# BEP33_rev1.net
KiCad netlist of a schematic drawn in EAGLE
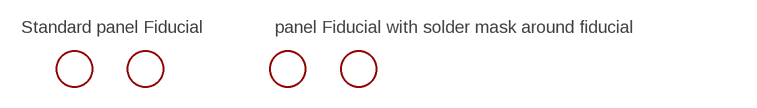
[diagram p0: schematic, sheet 1]
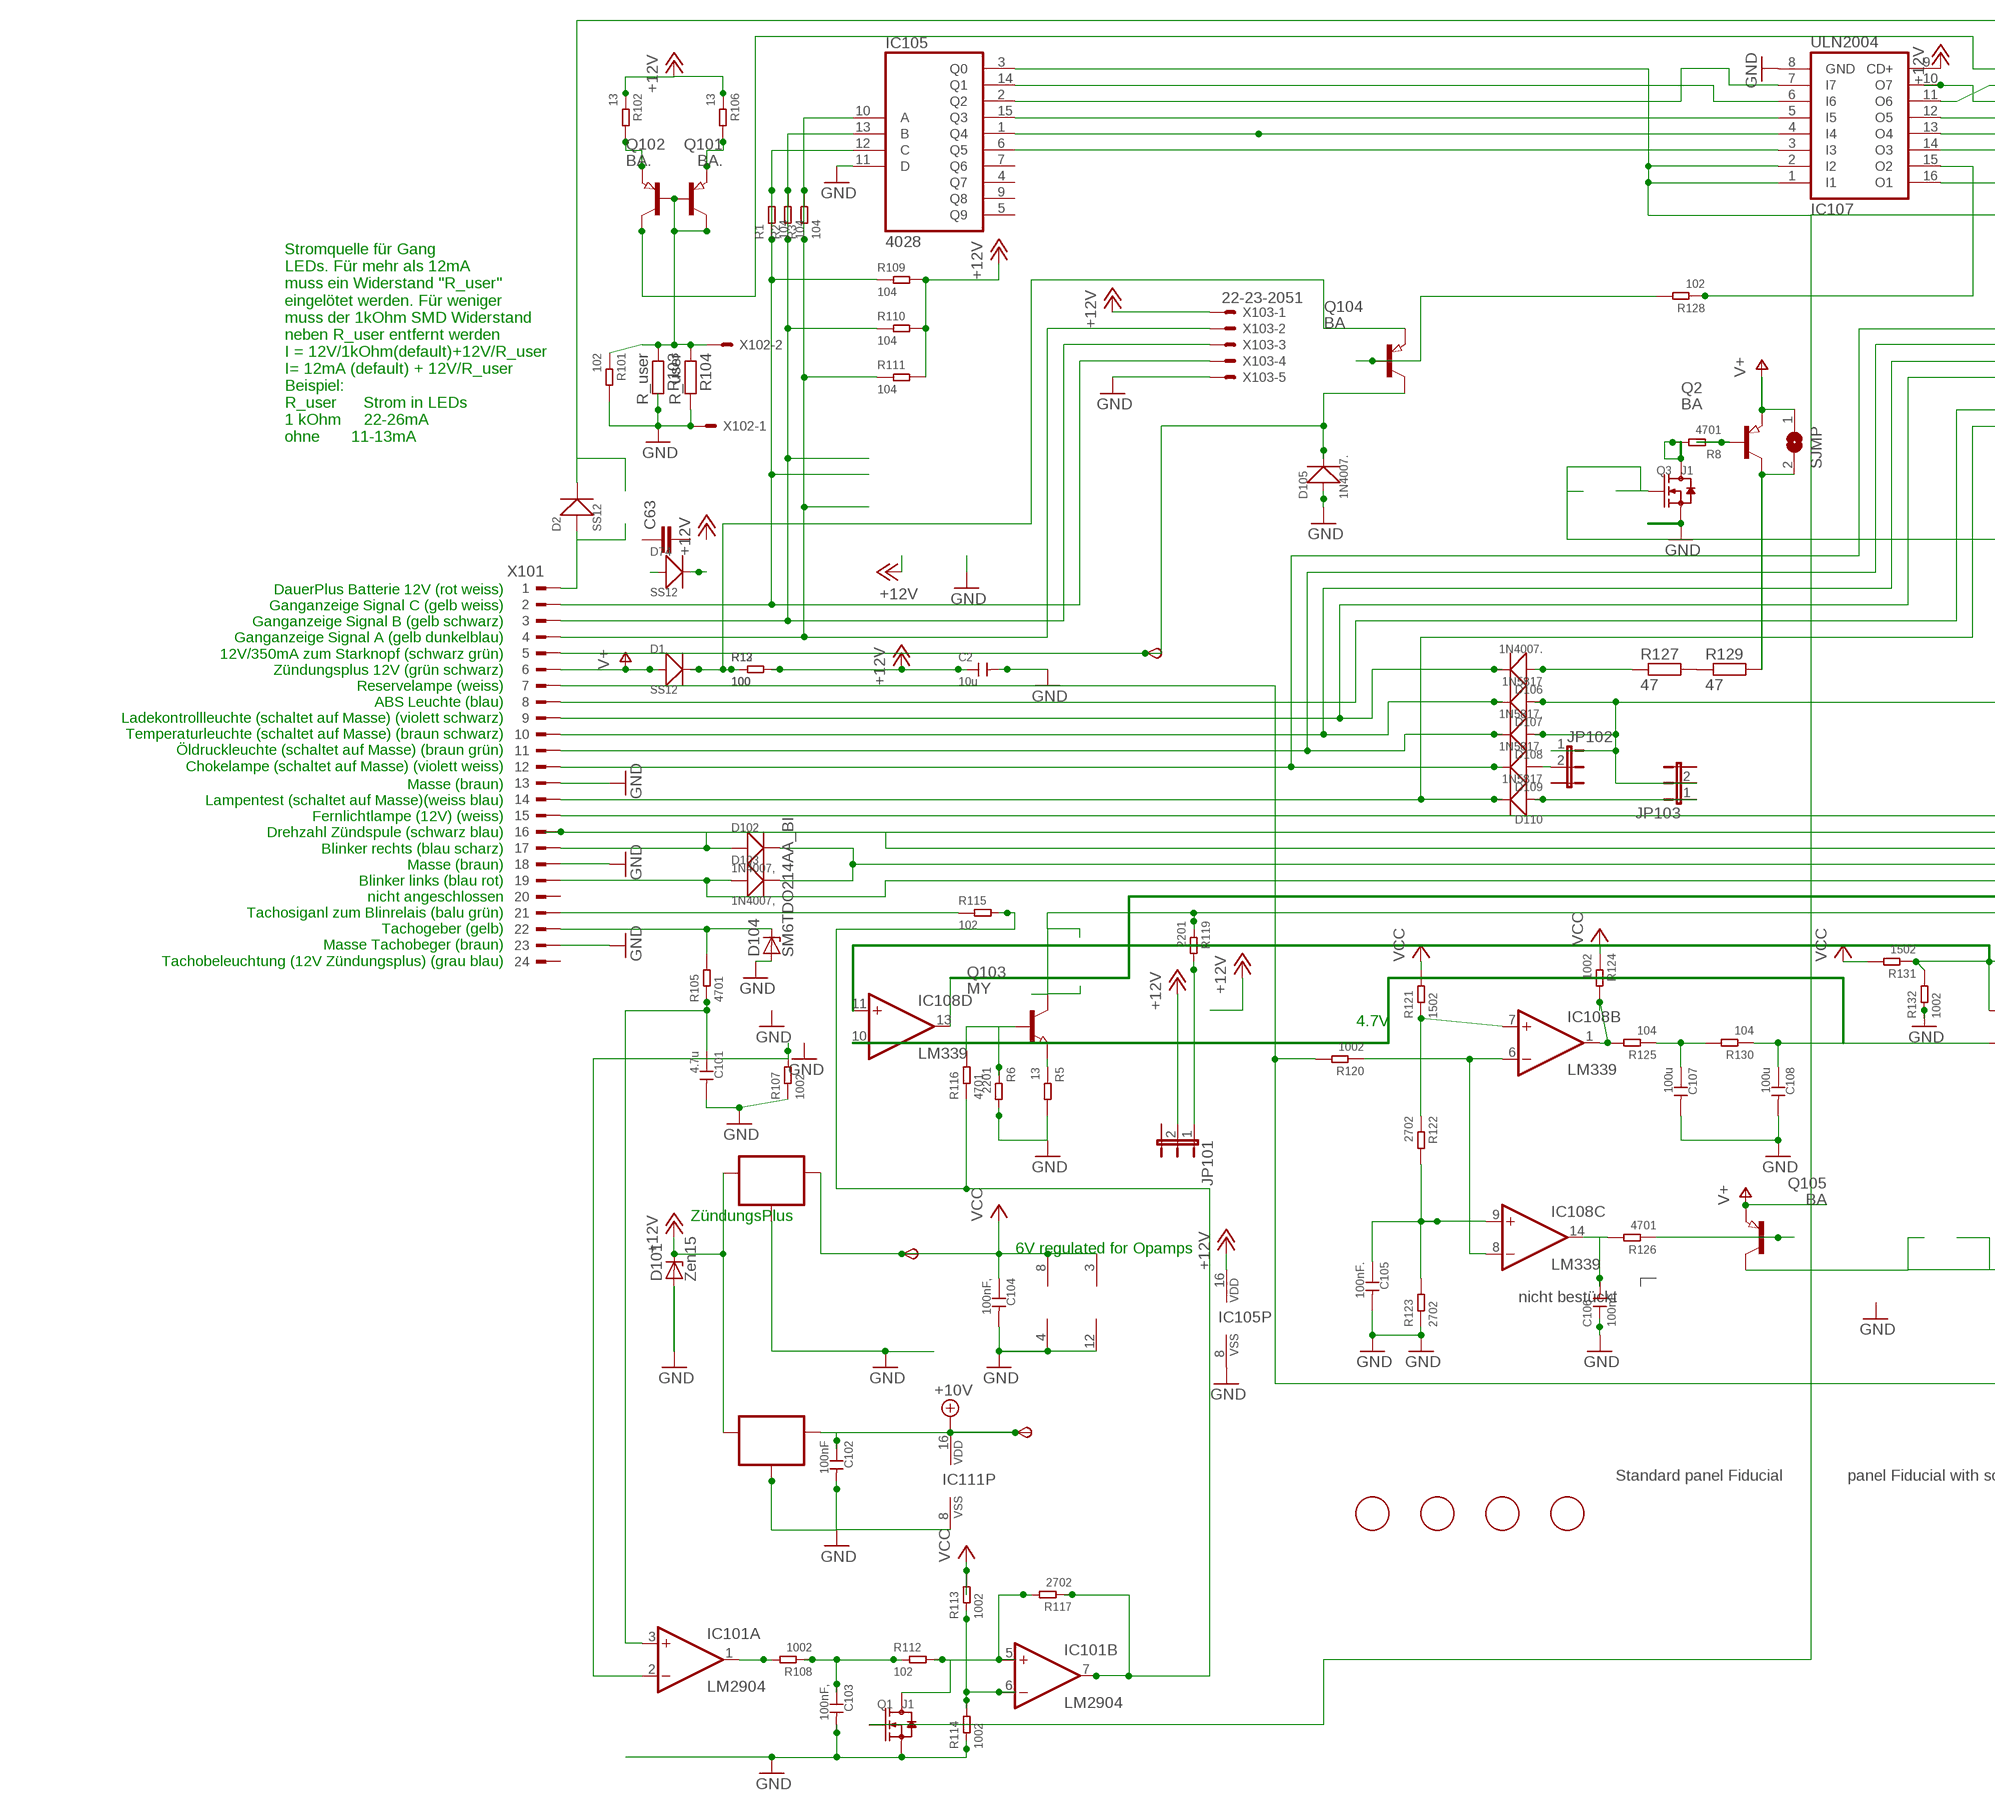
[diagram p1: schematic, sheet 2, part 1 of 2]
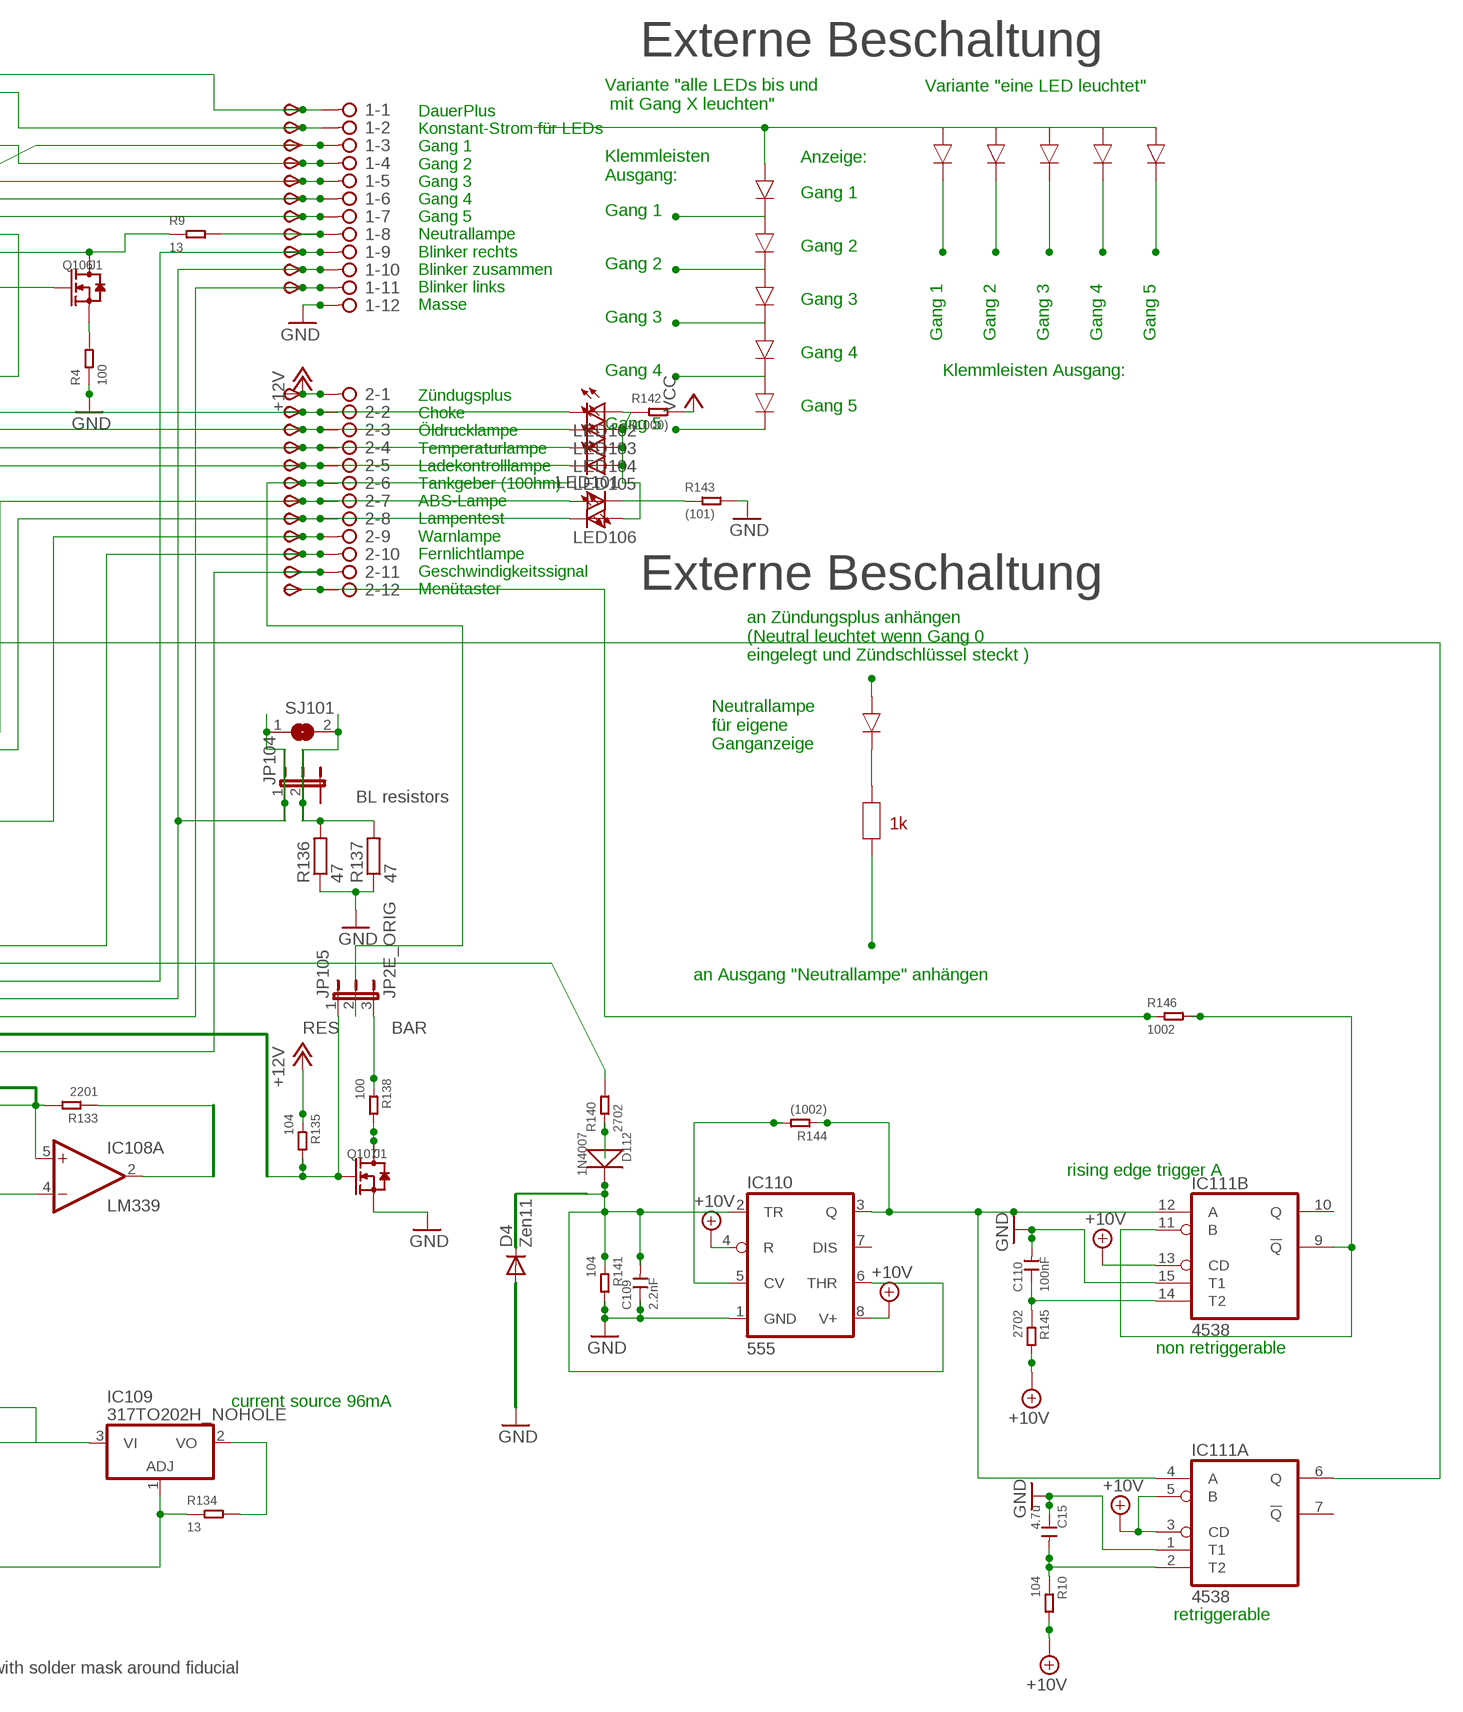
[diagram p2: schematic, sheet 2, part 2 of 2]
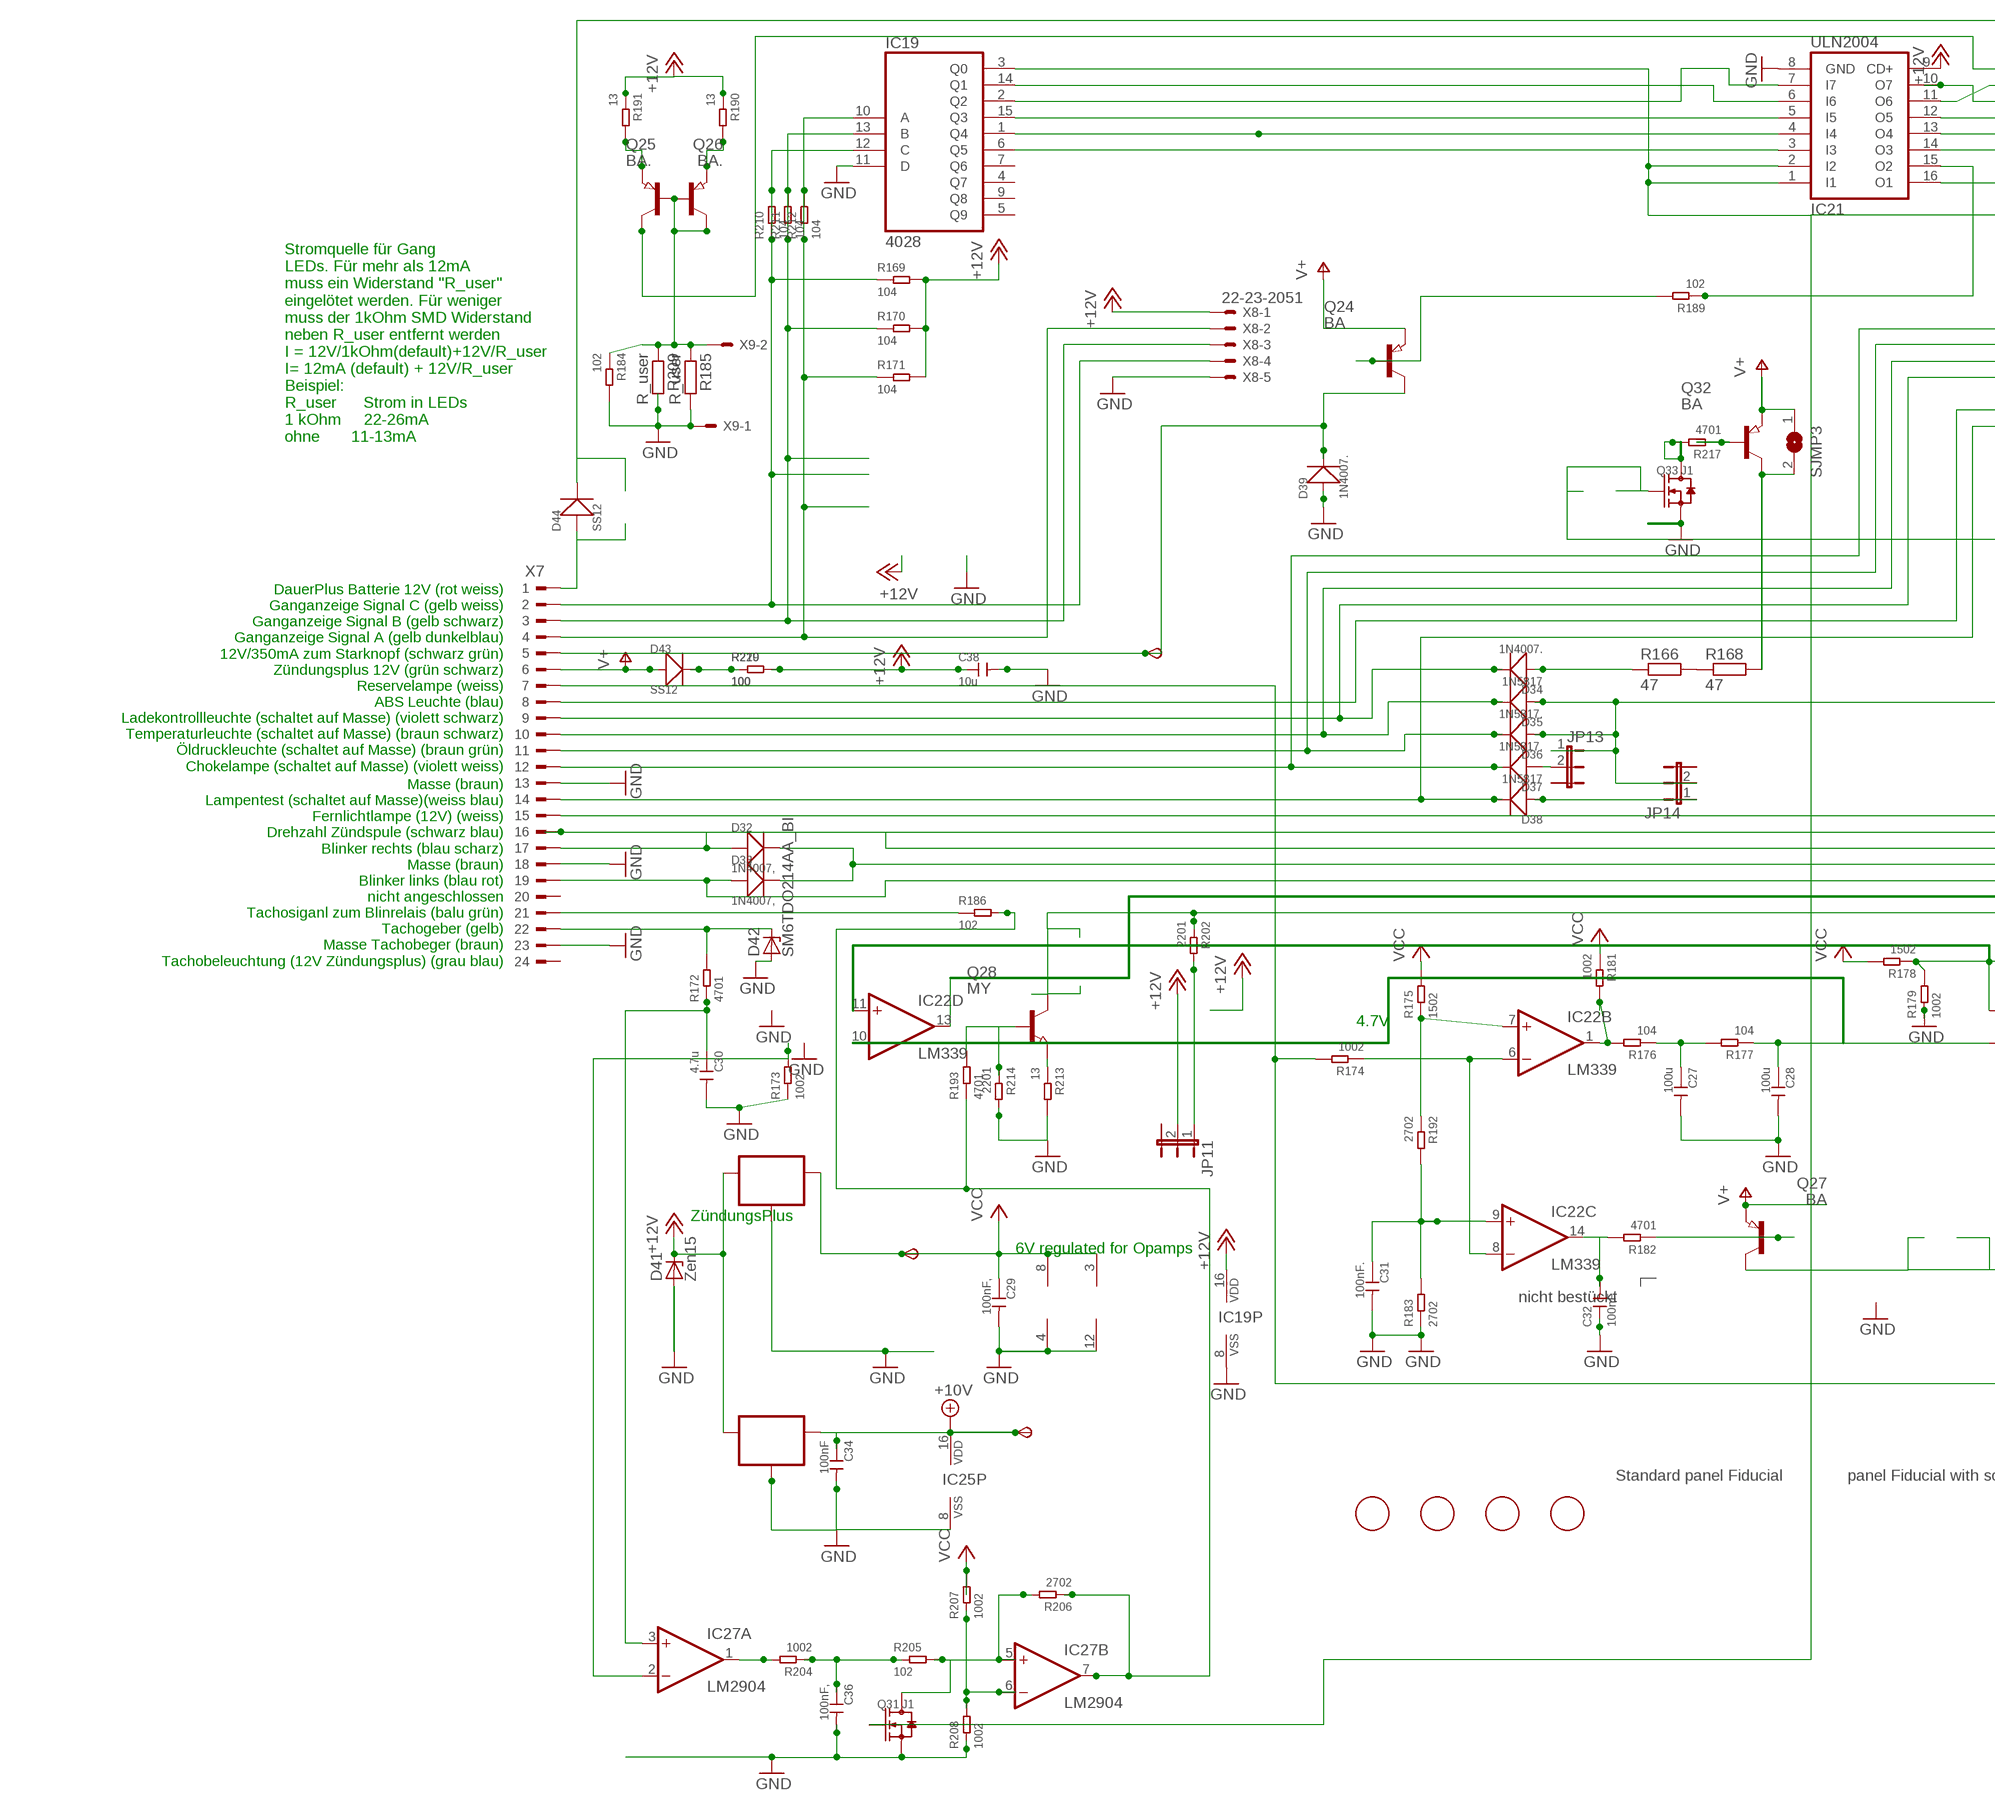
[diagram p3: schematic, sheet 3, part 1 of 2]
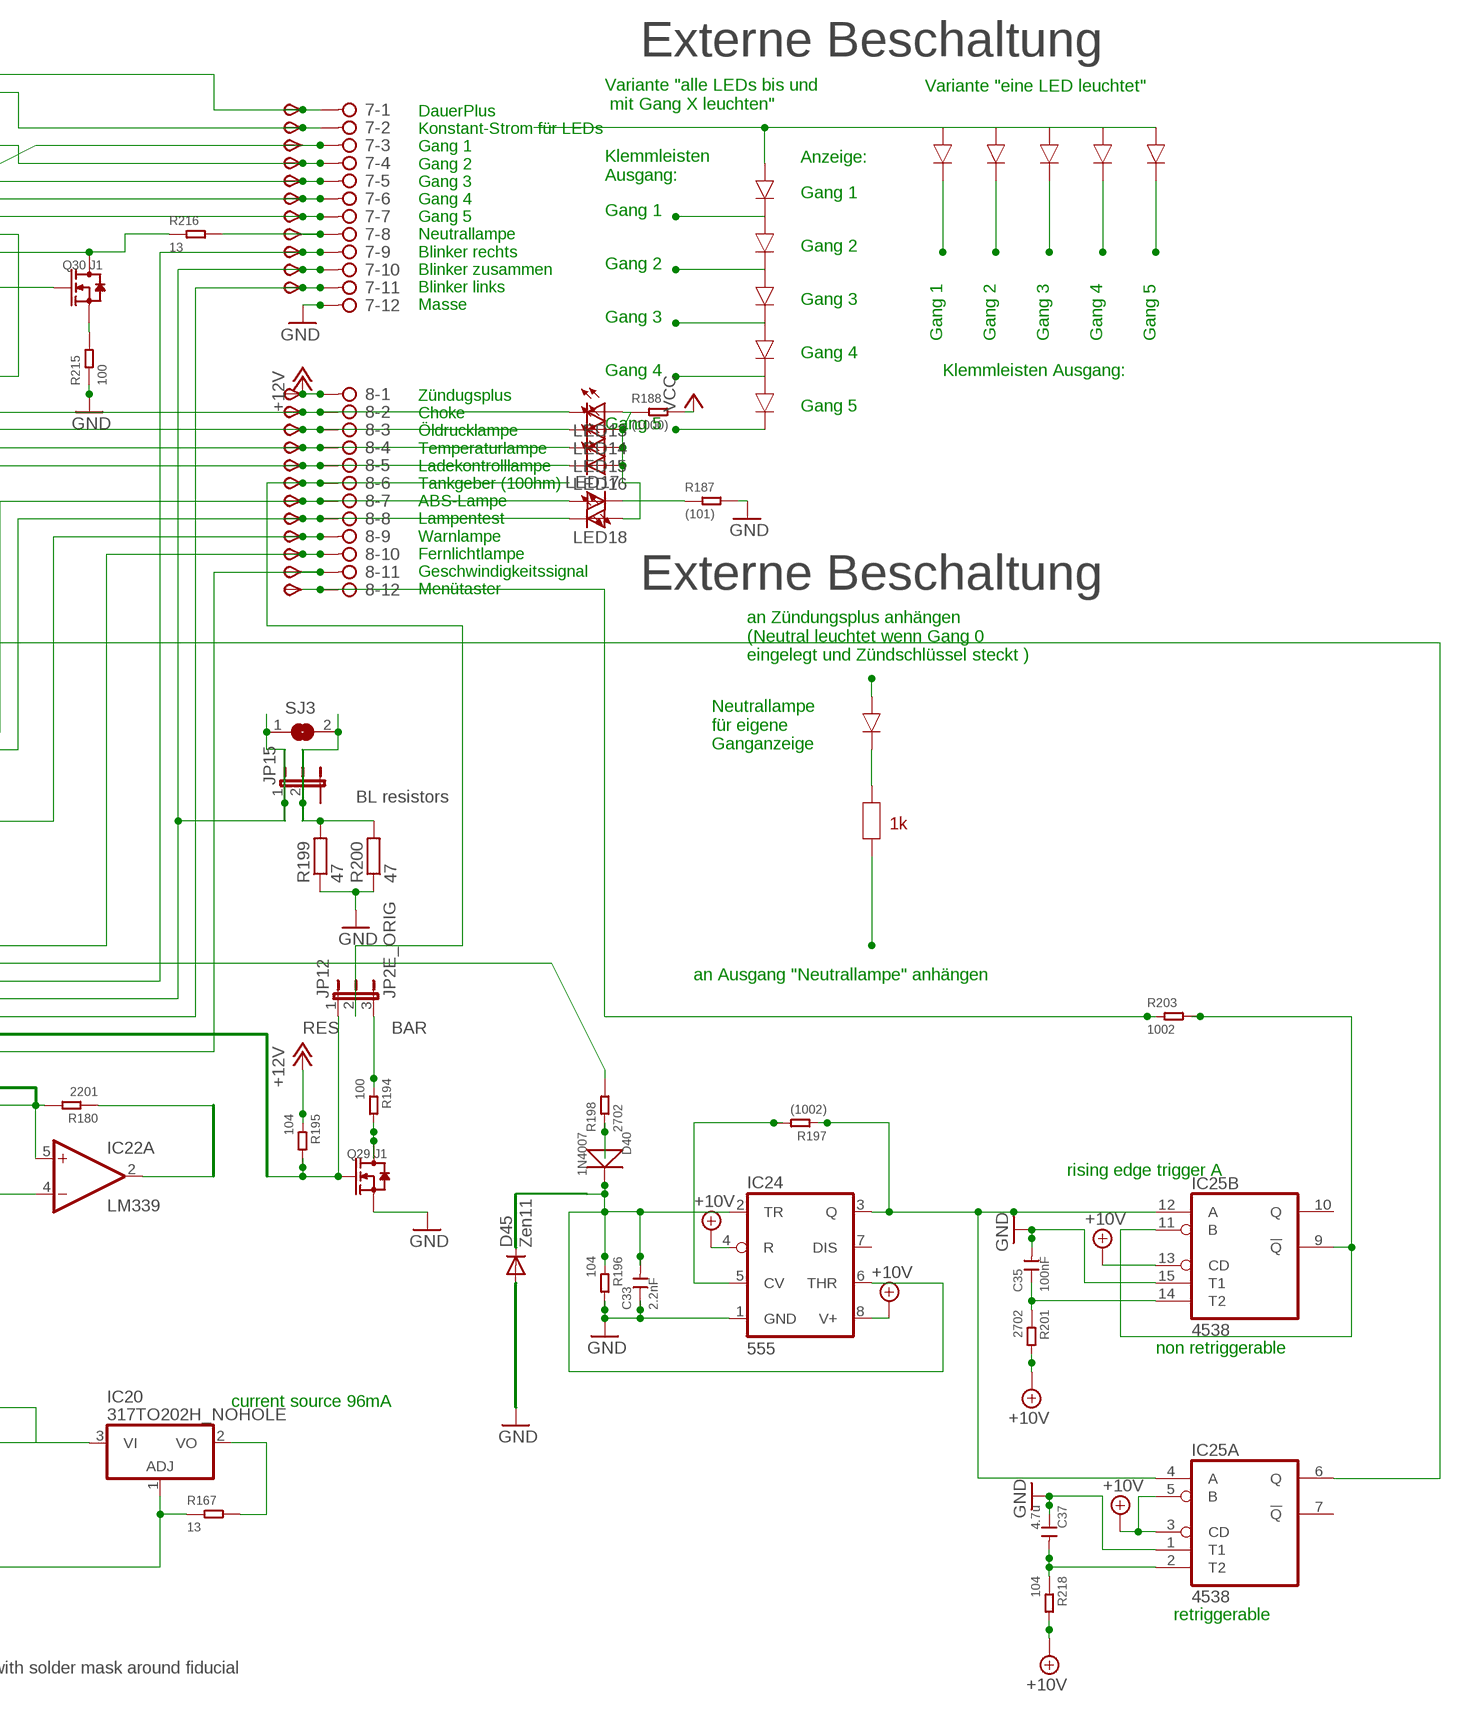
[diagram p4: schematic, sheet 3, part 2 of 2]

(export (version "E")
  (design (tool "Eeschema 10.0.6"))
  (components
    (comp (ref "1")
      (value "2081-1132")
      (footprint "eagle-import:12-PIN")
      (libsource (lib "eagle-import") (part "2081-1132"))
    )
    (comp (ref "2")
      (value "2081-1132")
      (footprint "eagle-import:12-PIN")
      (libsource (lib "eagle-import") (part "2081-1132"))
    )
    (comp (ref "6V")
      (value "TPSB2.0")
      (footprint "eagle-import:B2.0")
      (libsource (lib "eagle-import") (part "TPSB2.0"))
    )
    (comp (ref "10V")
      (value "TPSB2.0")
      (footprint "eagle-import:B2.0")
      (libsource (lib "eagle-import") (part "TPSB2.0"))
    )
    (comp (ref "C2")
      (value "10u")
      (footprint "eagle-import:C1206")
      (fields (field (name "MPN") "GRM31CR60J107ME39L"))
      (libsource (lib "eagle-import") (part "CERAMIC-100UF-6.3V-20%-X5R(1206)"))
    )
    (comp (ref "C15")
      (value "4.7u")
      (footprint "eagle-import:C0805")
      (fields (field (name "MPN") "CC0805KKX5R8BB475"))
      (libsource (lib "eagle-import") (part "CERAMIC-4.7UF-25V-10%-X5R(0805)"))
    )
    (comp (ref "C63")
      (value "C-EUC1812K")
      (footprint "eagle-import:C1812K")
      (libsource (lib "eagle-import") (part "C-EUC1812K"))
    )
    (comp (ref "C101")
      (value "4.7u")
      (footprint "eagle-import:C0805")
      (fields (field (name "MPN") "CC0805KKX5R8BB475"))
      (libsource (lib "eagle-import") (part "CERAMIC-4.7UF-25V-10%-X5R(0805)"))
    )
    (comp (ref "C102")
      (value "100nF")
      (footprint "eagle-import:C0805")
      (fields (field (name "MPN") "CC0805KRX7R9BB104"))
      (libsource (lib "eagle-import") (part "CERAMIC-100NF-50V-10%-X7R(0805)"))
    )
    (comp (ref "C103")
      (value "100nF,")
      (footprint "eagle-import:C0805")
      (fields (field (name "MPN") "CC0805KRX7R9BB104"))
      (libsource (lib "eagle-import") (part "CERAMIC-100NF-50V-10%-X7R(0805)"))
    )
    (comp (ref "C104")
      (value "100nF,")
      (footprint "eagle-import:C0805")
      (fields (field (name "MPN") "CC0805KRX7R9BB104"))
      (libsource (lib "eagle-import") (part "CERAMIC-100NF-50V-10%-X7R(0805)"))
    )
    (comp (ref "C105")
      (value "100nF.")
      (footprint "eagle-import:C0805")
      (fields (field (name "MPN") "CC0805KRX7R9BB104"))
      (libsource (lib "eagle-import") (part "CERAMIC-100NF-50V-10%-X7R(0805)"))
    )
    (comp (ref "C106")
      (value "100nF.")
      (footprint "eagle-import:C0805")
      (fields (field (name "MPN") "CC0805KRX7R9BB104"))
      (libsource (lib "eagle-import") (part "CERAMIC-100NF-50V-10%-X7R(0805)"))
    )
    (comp (ref "C107")
      (value "100u")
      (footprint "eagle-import:C1206")
      (fields (field (name "MPN") "GRM31CR60J107ME39L"))
      (libsource (lib "eagle-import") (part "CERAMIC-100UF-6.3V-20%-X5R(1206)"))
    )
    (comp (ref "C108")
      (value "100u")
      (footprint "eagle-import:C1206")
      (fields (field (name "MPN") "GRM31CR60J107ME39L"))
      (libsource (lib "eagle-import") (part "CERAMIC-100UF-6.3V-20%-X5R(1206)"))
    )
    (comp (ref "C109")
      (value "2.2nF")
      (footprint "eagle-import:C0805")
      (fields (field (name "MPN") "CC0805KRX7R9BB104"))
      (libsource (lib "eagle-import") (part "CERAMIC-100NF-50V-10%-X7R(0805)"))
    )
    (comp (ref "C110")
      (value "100nF")
      (footprint "eagle-import:C0805")
      (fields (field (name "MPN") "CC0805KRX7R9BB104"))
      (libsource (lib "eagle-import") (part "CERAMIC-100NF-50V-10%-X7R(0805)"))
    )
    (comp (ref "D1")
      (value "SS12")
      (footprint "eagle-import:DO-214AC_SLIM")
      (libsource (lib "eagle-import") (part "DIODE-GEN-PURPOSE-1KV-1A(DO-214AC)DO-214AC/1206"))
    )
    (comp (ref "D2")
      (value "SS12")
      (footprint "eagle-import:DO-214AC_SLIM")
      (libsource (lib "eagle-import") (part "DIODE-GEN-PURPOSE-1KV-1A(DO-214AC)DO-214AC/1206"))
    )
    (comp (ref "D4")
      (value "Zen11")
      (footprint "eagle-import:SOD-123_MINI-SMA")
      (libsource (lib "eagle-import") (part "CGRM400-G1"))
    )
    (comp (ref "D74")
      (value "SS12")
      (footprint "eagle-import:DO-214AC_SLIM")
      (libsource (lib "eagle-import") (part "DIODE-GEN-PURPOSE-1KV-1A(DO-214AC)DO-214AC/1206"))
    )
    (comp (ref "D101")
      (value "Zen15")
      (footprint "eagle-import:DO214AA")
      (libsource (lib "eagle-import") (part "SM6T"))
    )
    (comp (ref "D102")
      (value "1N4007,")
      (footprint "eagle-import:DO-214AC")
      (fields (field (name "MPN") "1N4007"))
      (libsource (lib "eagle-import") (part "DIODE-GEN-PURPOSE-1KV-1A(DO-214AC)"))
    )
    (comp (ref "D103")
      (value "1N4007,")
      (footprint "eagle-import:DO-214AC")
      (fields (field (name "MPN") "1N4007"))
      (libsource (lib "eagle-import") (part "DIODE-GEN-PURPOSE-1KV-1A(DO-214AC)"))
    )
    (comp (ref "D104")
      (value "SM6TDO214AA_BI")
      (footprint "eagle-import:DO214AA_BI")
      (libsource (lib "eagle-import") (part "SM6TDO214AA_BI"))
    )
    (comp (ref "D105")
      (value "1N4007.")
      (footprint "eagle-import:DO-214AC")
      (fields (field (name "MPN") "1N4007"))
      (libsource (lib "eagle-import") (part "DIODE-GEN-PURPOSE-1KV-1A(DO-214AC)"))
    )
    (comp (ref "D106")
      (value "1N4007.")
      (footprint "eagle-import:DO-214AC")
      (fields (field (name "MPN") "1N4007"))
      (libsource (lib "eagle-import") (part "DIODE-GEN-PURPOSE-1KV-1A(DO-214AC)"))
    )
    (comp (ref "D107")
      (value "1N5817")
      (footprint "eagle-import:DO-214AC_SLIM")
      (libsource (lib "eagle-import") (part "DIODE-GEN-PURPOSE-1KV-1A(DO-214AC)DO-214AC/1206"))
    )
    (comp (ref "D108")
      (value "1N5817.")
      (footprint "eagle-import:DO-214AC_SLIM")
      (libsource (lib "eagle-import") (part "DIODE-GEN-PURPOSE-1KV-1A(DO-214AC)DO-214AC/1206"))
    )
    (comp (ref "D109")
      (value "1N5817.")
      (footprint "eagle-import:DO-214AC_SLIM")
      (libsource (lib "eagle-import") (part "DIODE-GEN-PURPOSE-1KV-1A(DO-214AC)DO-214AC/1206"))
    )
    (comp (ref "D110")
      (value "1N5817")
      (footprint "eagle-import:DO-214AC_SLIM")
      (libsource (lib "eagle-import") (part "DIODE-GEN-PURPOSE-1KV-1A(DO-214AC)DO-214AC/1206"))
    )
    (comp (ref "D112")
      (value "1N4007")
      (footprint "eagle-import:DO-214AC")
      (libsource (lib "eagle-import") (part "DIODE-GEN-PURPOSE-1KV-1A(DO-214AC)"))
    )
    (comp (ref "FID101")
      (value "FIDUCIAL")
      (footprint "eagle-import:FIDUCIAL_1MM")
      (libsource (lib "eagle-import") (part "FIDUCIAL"))
    )
    (comp (ref "FID102")
      (value "FIDUCIAL")
      (footprint "eagle-import:FIDUCIAL_1MM")
      (libsource (lib "eagle-import") (part "FIDUCIAL"))
    )
    (comp (ref "FID103")
      (value "FIDUCIAL")
      (footprint "eagle-import:FIDUCIAL_1MM")
      (libsource (lib "eagle-import") (part "FIDUCIAL"))
    )
    (comp (ref "FID104")
      (value "FIDUCIAL")
      (footprint "eagle-import:FIDUCIAL_1MM")
      (libsource (lib "eagle-import") (part "FIDUCIAL"))
    )
    (comp (ref "IC101")
      (value "LM2904")
      (footprint "eagle-import:SO08")
      (libsource (lib "eagle-import") (part "LM358D"))
    )
    (comp (ref "IC102")
      (value "78L06")
      (footprint "eagle-import:SOT89_ROUND")
      (libsource (lib "eagle-import") (part "78LXXSOT89_ROUND"))
    )
    (comp (ref "IC104")
      (value "78L10")
      (footprint "eagle-import:SOT89_ROUND")
      (libsource (lib "eagle-import") (part "78LXXSOT89_ROUND"))
    )
    (comp (ref "IC105")
      (value "4028")
      (footprint "eagle-import:SO16")
      (libsource (lib "eagle-import") (part "4028D"))
    )
    (comp (ref "IC107")
      (value "ULN2004")
      (footprint "eagle-import:SO16")
      (libsource (lib "eagle-import") (part "ULN2004AD"))
    )
    (comp (ref "IC108")
      (value "LM339")
      (footprint "eagle-import:SO14")
      (libsource (lib "eagle-import") (part "LM339D"))
    )
    (comp (ref "IC109")
      (value "317TO202H_NOHOLE")
      (footprint "eagle-import:TO220H_NOHOLE")
      (libsource (lib "eagle-import") (part "317TO202H_NOHOLE"))
    )
    (comp (ref "IC110")
      (value "555")
      (footprint "eagle-import:SO08")
      (libsource (lib "eagle-import") (part "555DNE"))
    )
    (comp (ref "IC111")
      (value "4538")
      (footprint "eagle-import:SO16")
      (libsource (lib "eagle-import") (part "4538D"))
    )
    (comp (ref "JP101")
      (value "JP2EJP2_SMALLPADS")
      (footprint "eagle-import:JP2_SMALLPADS")
      (libsource (lib "eagle-import") (part "JP2EJP2_SMALLPADS"))
    )
    (comp (ref "JP102")
      (value "JP2EJP2_SMALLPADS")
      (footprint "eagle-import:JP2_SMALLPADS")
      (libsource (lib "eagle-import") (part "JP2EJP2_SMALLPADS"))
    )
    (comp (ref "JP103")
      (value "JP2EJP2_SMALLPADS")
      (footprint "eagle-import:JP2_SMALLPADS")
      (libsource (lib "eagle-import") (part "JP2EJP2_SMALLPADS"))
    )
    (comp (ref "JP104")
      (value "JP2EJP2_SMALLPADS")
      (footprint "eagle-import:JP2_SMALLPADS")
      (libsource (lib "eagle-import") (part "JP2EJP2_SMALLPADS"))
    )
    (comp (ref "JP105")
      (value "JP2E_ORIG")
      (footprint "eagle-import:JP2_ORIG_SMALLPADS")
      (libsource (lib "eagle-import") (part "JP2E_ORIG"))
    )
    (comp (ref "LED101")
      (value "LEDLD260")
      (footprint "eagle-import:LD260")
      (libsource (lib "eagle-import") (part "LEDLD260"))
    )
    (comp (ref "LED102")
      (value "LEDLD260")
      (footprint "eagle-import:LD260")
      (libsource (lib "eagle-import") (part "LEDLD260"))
    )
    (comp (ref "LED103")
      (value "LEDLD260")
      (footprint "eagle-import:LD260")
      (libsource (lib "eagle-import") (part "LEDLD260"))
    )
    (comp (ref "LED104")
      (value "LEDLD260")
      (footprint "eagle-import:LD260")
      (libsource (lib "eagle-import") (part "LEDLD260"))
    )
    (comp (ref "LED105")
      (value "LEDLD260")
      (footprint "eagle-import:LD260")
      (libsource (lib "eagle-import") (part "LEDLD260"))
    )
    (comp (ref "LED106")
      (value "LEDLD260")
      (footprint "eagle-import:LD260")
      (libsource (lib "eagle-import") (part "LEDLD260"))
    )
    (comp (ref "Q1")
      (value "J1")
      (footprint "eagle-import:SOT-23")
      (fields (field (name "MPN") "BSS138W-7-F"))
      (libsource (lib "eagle-import") (part "SMD-MOSFET-N-CH-50V-200MA-BSS138W-7-F(SOT-23)"))
    )
    (comp (ref "Q2")
      (value "BA")
      (footprint "eagle-import:SOT89")
      (libsource (lib "eagle-import") (part "PNP-TRANSISTOR_SOT89"))
    )
    (comp (ref "Q3")
      (value "J1")
      (footprint "eagle-import:SOT-23")
      (fields (field (name "MPN") "BSS138W-7-F"))
      (libsource (lib "eagle-import") (part "SMD-MOSFET-N-CH-50V-200MA-BSS138W-7-F(SOT-23)"))
    )
    (comp (ref "Q101")
      (value "BA.")
      (footprint "eagle-import:SOT89")
      (libsource (lib "eagle-import") (part "PNP-TRANSISTOR_SOT89"))
    )
    (comp (ref "Q102")
      (value "BA.")
      (footprint "eagle-import:SOT89")
      (libsource (lib "eagle-import") (part "PNP-TRANSISTOR_SOT89"))
    )
    (comp (ref "Q103")
      (value "MY")
      (footprint "eagle-import:SOT89")
      (libsource (lib "eagle-import") (part "NPN-TRANSISTOR_SOT89"))
    )
    (comp (ref "Q104")
      (value "BA")
      (footprint "eagle-import:SOT89")
      (libsource (lib "eagle-import") (part "PNP-TRANSISTOR_SOT89"))
    )
    (comp (ref "Q105")
      (value "BA")
      (footprint "eagle-import:SOT89")
      (libsource (lib "eagle-import") (part "PNP-TRANSISTOR_SOT89"))
    )
    (comp (ref "Q106")
      (value "J1")
      (footprint "eagle-import:SOT-23")
      (fields (field (name "MPN") "BSS138W-7-F"))
      (libsource (lib "eagle-import") (part "SMD-MOSFET-N-CH-50V-200MA-BSS138W-7-F(SOT-23)"))
    )
    (comp (ref "Q107")
      (value "J1")
      (footprint "eagle-import:SOT-23")
      (fields (field (name "MPN") "BSS138W-7-F"))
      (libsource (lib "eagle-import") (part "SMD-MOSFET-N-CH-50V-200MA-BSS138W-7-F(SOT-23)"))
    )
    (comp (ref "R1")
      (value "104")
      (footprint "eagle-import:R0805")
      (fields (field (name "MPN") "RC0805FR-0710KL"))
      (libsource (lib "eagle-import") (part "SMD-RES-10K-1%-1/8W(0805)"))
    )
    (comp (ref "R2")
      (value "104")
      (footprint "eagle-import:R0805")
      (fields (field (name "MPN") "RC0805FR-0710KL"))
      (libsource (lib "eagle-import") (part "SMD-RES-10K-1%-1/8W(0805)"))
    )
    (comp (ref "R3")
      (value "104")
      (footprint "eagle-import:R0805")
      (fields (field (name "MPN") "RC0805FR-0710KL"))
      (libsource (lib "eagle-import") (part "SMD-RES-10K-1%-1/8W(0805)"))
    )
    (comp (ref "R4")
      (value "100")
      (footprint "eagle-import:R0805")
      (fields (field (name "MPN") "RC0805JR-07220RL"))
      (libsource (lib "eagle-import") (part "SMD-RES-220R-5%-1/8W(0805)"))
    )
    (comp (ref "R5")
      (value "13")
      (footprint "eagle-import:R1206")
      (fields (field (name "MPN") "RC1206JR-0713RL"))
      (libsource (lib "eagle-import") (part "SMD-RES-13R-5%-1/4W(1206)"))
    )
    (comp (ref "R6")
      (value "2201")
      (footprint "eagle-import:R0805")
      (fields (field (name "MPN") "RC0805JR-071KL"))
      (libsource (lib "eagle-import") (part "SMD-RES-1K-5%-1/8W(0805)"))
    )
    (comp (ref "R8")
      (value "4701")
      (footprint "eagle-import:R0805")
      (fields (field (name "MPN") "RC0805JR-074K7L"))
      (libsource (lib "eagle-import") (part "SMD-RES-4.7K-5%-1/8W(0805)"))
    )
    (comp (ref "R9")
      (value "13")
      (footprint "eagle-import:R1206")
      (fields (field (name "MPN") "RC1206JR-0713RL"))
      (libsource (lib "eagle-import") (part "SMD-RES-13R-5%-1/4W(1206)"))
    )
    (comp (ref "R10")
      (value "104")
      (footprint "eagle-import:R0805")
      (fields (field (name "MPN") "RC0805JR-074K7L"))
      (libsource (lib "eagle-import") (part "SMD-RES-4.7K-5%-1/8W(0805)"))
    )
    (comp (ref "R12")
      (value "100")
      (footprint "eagle-import:R0805")
      (fields (field (name "MPN") "RC0805JR-072K2L"))
      (libsource (lib "eagle-import") (part "SMD-RES-2.2K-5%-1/8W(0805)"))
    )
    (comp (ref "R13")
      (value "100")
      (footprint "eagle-import:R0805")
      (fields (field (name "MPN") "RC0805JR-072K2L"))
      (libsource (lib "eagle-import") (part "SMD-RES-2.2K-5%-1/8W(0805)"))
    )
    (comp (ref "R101")
      (value "102")
      (footprint "eagle-import:R0805")
      (fields (field (name "MPN") "RC0805JR-071KL"))
      (libsource (lib "eagle-import") (part "SMD-RES-1K-5%-1/8W(0805)"))
    )
    (comp (ref "R102")
      (value "13")
      (footprint "eagle-import:R1206")
      (fields (field (name "MPN") "RC1206JR-0713RL"))
      (libsource (lib "eagle-import") (part "SMD-RES-13R-5%-1/4W(1206)"))
    )
    (comp (ref "R103")
      (value "R_user")
      (footprint "eagle-import:R0805")
      (libsource (lib "eagle-import") (part "R-EU_R0805"))
    )
    (comp (ref "R104")
      (value "R_user")
      (footprint "eagle-import:R0805")
      (libsource (lib "eagle-import") (part "R-EU_R0805"))
    )
    (comp (ref "R105")
      (value "4701")
      (footprint "eagle-import:R0805")
      (fields (field (name "MPN") "RC0805JR-074K7L"))
      (libsource (lib "eagle-import") (part "SMD-RES-4.7K-5%-1/8W(0805)"))
    )
    (comp (ref "R106")
      (value "13")
      (footprint "eagle-import:R1206")
      (fields (field (name "MPN") "RC1206JR-0713RL"))
      (libsource (lib "eagle-import") (part "SMD-RES-13R-5%-1/4W(1206)"))
    )
    (comp (ref "R107")
      (value "1002")
      (footprint "eagle-import:R0805")
      (fields (field (name "MPN") "RC0805FR-0710KL"))
      (libsource (lib "eagle-import") (part "SMD-RES-10K-1%-1/8W(0805)"))
    )
    (comp (ref "R108")
      (value "1002")
      (footprint "eagle-import:R0805")
      (fields (field (name "MPN") "RC0805FR-0710KL"))
      (libsource (lib "eagle-import") (part "SMD-RES-10K-1%-1/8W(0805)"))
    )
    (comp (ref "R109")
      (value "104")
      (footprint "eagle-import:R0805")
      (fields (field (name "MPN") "RC0805FR-0710KL"))
      (libsource (lib "eagle-import") (part "SMD-RES-10K-1%-1/8W(0805)"))
    )
    (comp (ref "R110")
      (value "104")
      (footprint "eagle-import:R0805")
      (fields (field (name "MPN") "RC0805FR-0710KL"))
      (libsource (lib "eagle-import") (part "SMD-RES-10K-1%-1/8W(0805)"))
    )
    (comp (ref "R111")
      (value "104")
      (footprint "eagle-import:R0805")
      (fields (field (name "MPN") "RC0805FR-0710KL"))
      (libsource (lib "eagle-import") (part "SMD-RES-10K-1%-1/8W(0805)"))
    )
    (comp (ref "R112")
      (value "102")
      (footprint "eagle-import:R0805")
      (fields (field (name "MPN") "RC0805JR-071KL"))
      (libsource (lib "eagle-import") (part "SMD-RES-1K-5%-1/8W(0805)"))
    )
    (comp (ref "R113")
      (value "1002")
      (footprint "eagle-import:R0805")
      (fields (field (name "MPN") "RC0805JR-071KL"))
      (libsource (lib "eagle-import") (part "SMD-RES-1K-5%-1/8W(0805)"))
    )
    (comp (ref "R114")
      (value "1002")
      (footprint "eagle-import:R0805")
      (fields (field (name "MPN") "RC0805JR-071KL"))
      (libsource (lib "eagle-import") (part "SMD-RES-1K-5%-1/8W(0805)"))
    )
    (comp (ref "R115")
      (value "102")
      (footprint "eagle-import:R0805")
      (fields (field (name "MPN") "RC0805JR-07220RL"))
      (libsource (lib "eagle-import") (part "SMD-RES-220R-5%-1/8W(0805)"))
    )
    (comp (ref "R116")
      (value "4701")
      (footprint "eagle-import:R0805")
      (fields (field (name "MPN") "RC0805JR-074K7L"))
      (libsource (lib "eagle-import") (part "SMD-RES-4.7K-5%-1/8W(0805)"))
    )
    (comp (ref "R117")
      (value "2702")
      (footprint "eagle-import:R0805")
      (fields (field (name "MPN") "RC0805JR-074K7L"))
      (libsource (lib "eagle-import") (part "SMD-RES-4.7K-5%-1/8W(0805)"))
    )
    (comp (ref "R119")
      (value "2201")
      (footprint "eagle-import:R0805")
      (fields (field (name "MPN") "RC0805JR-072K2L"))
      (libsource (lib "eagle-import") (part "SMD-RES-2.2K-5%-1/8W(0805)"))
    )
    (comp (ref "R120")
      (value "1002")
      (footprint "eagle-import:R0805")
      (fields (field (name "MPN") "RC0805FR-0710KL"))
      (libsource (lib "eagle-import") (part "SMD-RES-10K-1%-1/8W(0805)"))
    )
    (comp (ref "R121")
      (value "1502")
      (footprint "eagle-import:R0805")
      (fields (field (name "MPN") "RC0805FR-0710KL"))
      (libsource (lib "eagle-import") (part "SMD-RES-10K-1%-1/8W(0805)"))
    )
    (comp (ref "R122")
      (value "2702")
      (footprint "eagle-import:R0805")
      (fields (field (name "MPN") "RC0805JR-074K7L"))
      (libsource (lib "eagle-import") (part "SMD-RES-4.7K-5%-1/8W(0805)"))
    )
    (comp (ref "R123")
      (value "2702")
      (footprint "eagle-import:R0805")
      (fields (field (name "MPN") "RC0805JR-074K7L"))
      (libsource (lib "eagle-import") (part "SMD-RES-4.7K-5%-1/8W(0805)"))
    )
    (comp (ref "R124")
      (value "1002")
      (footprint "eagle-import:R0805")
      (fields (field (name "MPN") "RC0805FR-0710KL"))
      (libsource (lib "eagle-import") (part "SMD-RES-10K-1%-1/8W(0805)"))
    )
    (comp (ref "R125")
      (value "104")
      (footprint "eagle-import:R0805")
      (fields (field (name "MPN") "RC0805FR-0710KL"))
      (libsource (lib "eagle-import") (part "SMD-RES-10K-1%-1/8W(0805)"))
    )
    (comp (ref "R126")
      (value "4701")
      (footprint "eagle-import:R0805")
      (fields (field (name "MPN") "RC0805JR-074K7L"))
      (libsource (lib "eagle-import") (part "SMD-RES-4.7K-5%-1/8W(0805)"))
    )
    (comp (ref "R127")
      (value "47")
      (footprint "eagle-import:V235_17_1MM")
      (libsource (lib "eagle-import") (part "R-EU_V235/17_1MM"))
    )
    (comp (ref "R128")
      (value "102")
      (footprint "eagle-import:R0805")
      (fields (field (name "MPN") "RC0805JR-071KL"))
      (libsource (lib "eagle-import") (part "SMD-RES-1K-5%-1/8W(0805)"))
    )
    (comp (ref "R129")
      (value "47")
      (footprint "eagle-import:V235_17_1MM")
      (libsource (lib "eagle-import") (part "R-EU_V235/17_1MM"))
    )
    (comp (ref "R130")
      (value "104")
      (footprint "eagle-import:R0805")
      (fields (field (name "MPN") "RC0805FR-0710KL"))
      (libsource (lib "eagle-import") (part "SMD-RES-10K-1%-1/8W(0805)"))
    )
    (comp (ref "R131")
      (value "1502")
      (footprint "eagle-import:R0805")
      (fields (field (name "MPN") "RC0805FR-0710KL"))
      (libsource (lib "eagle-import") (part "SMD-RES-10K-1%-1/8W(0805)"))
    )
    (comp (ref "R132")
      (value "1002")
      (footprint "eagle-import:R0805")
      (fields (field (name "MPN") "RC0805FR-0710KL"))
      (libsource (lib "eagle-import") (part "SMD-RES-10K-1%-1/8W(0805)"))
    )
    (comp (ref "R133")
      (value "2201")
      (footprint "eagle-import:R0805")
      (fields (field (name "MPN") "RC0805JR-072K2L"))
      (libsource (lib "eagle-import") (part "SMD-RES-2.2K-5%-1/8W(0805)"))
    )
    (comp (ref "R134")
      (value "13")
      (footprint "eagle-import:R1206")
      (fields (field (name "MPN") "RC1206JR-0713RL"))
      (libsource (lib "eagle-import") (part "SMD-RES-13R-5%-1/4W(1206)"))
    )
    (comp (ref "R135")
      (value "104")
      (footprint "eagle-import:R0805")
      (fields (field (name "MPN") "RC0805FR-0710KL"))
      (libsource (lib "eagle-import") (part "SMD-RES-10K-1%-1/8W(0805)"))
    )
    (comp (ref "R136")
      (value "47")
      (footprint "eagle-import:V235_17_1MM")
      (libsource (lib "eagle-import") (part "R-EU_V235/17_1MM"))
    )
    (comp (ref "R137")
      (value "47")
      (footprint "eagle-import:V235_17_1MM")
      (libsource (lib "eagle-import") (part "R-EU_V235/17_1MM"))
    )
    (comp (ref "R138")
      (value "100")
      (footprint "eagle-import:R0805")
      (fields (field (name "MPN") "RC0805JR-072K2L"))
      (libsource (lib "eagle-import") (part "SMD-RES-2.2K-5%-1/8W(0805)"))
    )
    (comp (ref "R140")
      (value "2702")
      (footprint "eagle-import:R0805")
      (fields (field (name "MPN") "RC0805FR-0710KL"))
      (libsource (lib "eagle-import") (part "SMD-RES-10K-1%-1/8W(0805)"))
    )
    (comp (ref "R141")
      (value "104")
      (footprint "eagle-import:R0805")
      (fields (field (name "MPN") "RC0805FR-0710KL"))
      (libsource (lib "eagle-import") (part "SMD-RES-10K-1%-1/8W(0805)"))
    )
    (comp (ref "R142")
      (value "(1000)")
      (footprint "eagle-import:R0805")
      (fields (field (name "MPN") "RC0805JR-07100RL"))
      (libsource (lib "eagle-import") (part "SMD-RES-100R-5%-1/8W(0805)"))
    )
    (comp (ref "R143")
      (value "(101)")
      (footprint "eagle-import:R0805")
      (fields (field (name "MPN") "RC0805JR-07100RL"))
      (libsource (lib "eagle-import") (part "SMD-RES-100R-5%-1/8W(0805)"))
    )
    (comp (ref "R144")
      (value "(1002)")
      (footprint "eagle-import:R0805")
      (fields (field (name "MPN") "RC0805FR-0710KL"))
      (libsource (lib "eagle-import") (part "SMD-RES-10K-1%-1/8W(0805)"))
    )
    (comp (ref "R145")
      (value "2702")
      (footprint "eagle-import:R0805")
      (fields (field (name "MPN") "RC0805JR-074K7L"))
      (libsource (lib "eagle-import") (part "SMD-RES-4.7K-5%-1/8W(0805)"))
    )
    (comp (ref "R146")
      (value "1002")
      (footprint "eagle-import:R0805")
      (fields (field (name "MPN") "RC0805JR-074K7L"))
      (libsource (lib "eagle-import") (part "SMD-RES-4.7K-5%-1/8W(0805)"))
    )
    (comp (ref "SJ101")
      (value "SJ")
      (footprint "eagle-import:SJ")
      (libsource (lib "eagle-import") (part "solder-jumper_SJ"))
    )
    (comp (ref "SJMP")
      (value "SJ")
      (footprint "eagle-import:SJ")
      (libsource (lib "eagle-import") (part "SJ"))
    )
    (comp (ref "START")
      (value "TPSB2.0")
      (footprint "eagle-import:B2.0")
      (libsource (lib "eagle-import") (part "TPSB2.0"))
    )
    (comp (ref "TP1")
      (value "TPSB2.0")
      (footprint "eagle-import:B2.0")
      (libsource (lib "eagle-import") (part "TPSB2.0"))
    )
    (comp (ref "TP2")
      (value "TPSB2.0")
      (footprint "eagle-import:B2.0")
      (libsource (lib "eagle-import") (part "TPSB2.0"))
    )
    (comp (ref "TP3")
      (value "TPSB2.0")
      (footprint "eagle-import:B2.0")
      (libsource (lib "eagle-import") (part "TPSB2.0"))
    )
    (comp (ref "TP4")
      (value "TPSB2.0")
      (footprint "eagle-import:B2.0")
      (libsource (lib "eagle-import") (part "TPSB2.0"))
    )
    (comp (ref "TP5")
      (value "TPSB2.0")
      (footprint "eagle-import:B2.0")
      (libsource (lib "eagle-import") (part "TPSB2.0"))
    )
    (comp (ref "TP6")
      (value "TPSB2.0")
      (footprint "eagle-import:B2.0")
      (libsource (lib "eagle-import") (part "TPSB2.0"))
    )
    (comp (ref "TP7")
      (value "TPSB2.0")
      (footprint "eagle-import:B2.0")
      (libsource (lib "eagle-import") (part "TPSB2.0"))
    )
    (comp (ref "TP8")
      (value "TPSB2.0")
      (footprint "eagle-import:B2.0")
      (libsource (lib "eagle-import") (part "TPSB2.0"))
    )
    (comp (ref "TP9")
      (value "TPSB2.0")
      (footprint "eagle-import:B2.0")
      (libsource (lib "eagle-import") (part "TPSB2.0"))
    )
    (comp (ref "TP10")
      (value "TPSB2.0")
      (footprint "eagle-import:B2.0")
      (libsource (lib "eagle-import") (part "TPSB2.0"))
    )
    (comp (ref "TP11")
      (value "TPSB2.0")
      (footprint "eagle-import:B2.0")
      (libsource (lib "eagle-import") (part "TPSB2.0"))
    )
    (comp (ref "TP12")
      (value "TPSB2.0")
      (footprint "eagle-import:B2.0")
      (libsource (lib "eagle-import") (part "TPSB2.0"))
    )
    (comp (ref "TP13")
      (value "TPSB2.0")
      (footprint "eagle-import:B2.0")
      (libsource (lib "eagle-import") (part "TPSB2.0"))
    )
    (comp (ref "TP16")
      (value "TPSB2.0")
      (footprint "eagle-import:B2.0")
      (libsource (lib "eagle-import") (part "TPSB2.0"))
    )
    (comp (ref "TP17")
      (value "TPSB2.0")
      (footprint "eagle-import:B2.0")
      (libsource (lib "eagle-import") (part "TPSB2.0"))
    )
    (comp (ref "TP18")
      (value "TPSB2.0")
      (footprint "eagle-import:B2.0")
      (libsource (lib "eagle-import") (part "TPSB2.0"))
    )
    (comp (ref "TP19")
      (value "TPSB2.0")
      (footprint "eagle-import:B2.0")
      (libsource (lib "eagle-import") (part "TPSB2.0"))
    )
    (comp (ref "TP21")
      (value "TPSB2.0")
      (footprint "eagle-import:B2.0")
      (libsource (lib "eagle-import") (part "TPSB2.0"))
    )
    (comp (ref "TP22")
      (value "TPSB2.0")
      (footprint "eagle-import:B2.0")
      (libsource (lib "eagle-import") (part "TPSB2.0"))
    )
    (comp (ref "TP23")
      (value "TPSB2.0")
      (footprint "eagle-import:B2.0")
      (libsource (lib "eagle-import") (part "TPSB2.0"))
    )
    (comp (ref "TP24")
      (value "TPSB1,27")
      (footprint "eagle-import:B1,27")
      (libsource (lib "eagle-import") (part "TPSB1,27"))
    )
    (comp (ref "TP25")
      (value "TPSB2.0")
      (footprint "eagle-import:B2.0")
      (libsource (lib "eagle-import") (part "TPSB2.0"))
    )
    (comp (ref "TP26")
      (value "TPSB2.0")
      (footprint "eagle-import:B2.0")
      (libsource (lib "eagle-import") (part "TPSB2.0"))
    )
    (comp (ref "X101")
      (value "CON_BMWV2")
      (footprint "eagle-import:24-PIN_V2")
      (libsource (lib "eagle-import") (part "CON_BMWV2"))
    )
    (comp (ref "X102")
      (value "22-23-2021")
      (footprint "eagle-import:22-23-2021")
      (fields (field (name "MF") "MOLEX"))
      (libsource (lib "eagle-import") (part "22-23-2021"))
    )
    (comp (ref "X103")
      (value "22-23-2051")
      (footprint "eagle-import:22-23-2051")
      (fields (field (name "MF") "MOLEX"))
      (libsource (lib "eagle-import") (part "22-23-2051"))
    )
    (comp (ref "FID1")
      (value "FIDUCIAL")
      (footprint "eagle-import:FIDUCIAL_1MM")
      (libsource (lib "eagle-import") (part "FIDUCIAL"))
    )
    (comp (ref "FID1B")
      (value "FIDUCIALFIDUCIAL_1MM_WITH_SOLDERMASK")
      (footprint "eagle-import:FIDUCIAL_1MM_WITH_SOLDERMASK")
      (libsource (lib "eagle-import") (part "FIDUCIALFIDUCIAL_1MM_WITH_SOLDERMASK"))
    )
    (comp (ref "FID2")
      (value "FIDUCIAL")
      (footprint "eagle-import:FIDUCIAL_1MM")
      (libsource (lib "eagle-import") (part "FIDUCIAL"))
    )
    (comp (ref "FID2B")
      (value "FIDUCIALFIDUCIAL_1MM_WITH_SOLDERMASK")
      (footprint "eagle-import:FIDUCIAL_1MM_WITH_SOLDERMASK")
      (libsource (lib "eagle-import") (part "FIDUCIALFIDUCIAL_1MM_WITH_SOLDERMASK"))
    )
    (comp (ref "6V3")
      (value "TPSB2.0")
      (footprint "eagle-import:B2.0")
      (libsource (lib "eagle-import") (part "TPSB2.0"))
    )
    (comp (ref "7")
      (value "2081-1132")
      (footprint "eagle-import:12-PIN")
      (libsource (lib "eagle-import") (part "2081-1132"))
    )
    (comp (ref "8")
      (value "2081-1132")
      (footprint "eagle-import:12-PIN")
      (libsource (lib "eagle-import") (part "2081-1132"))
    )
    (comp (ref "10V3")
      (value "TPSB2.0")
      (footprint "eagle-import:B2.0")
      (libsource (lib "eagle-import") (part "TPSB2.0"))
    )
    (comp (ref "C27")
      (value "100u")
      (footprint "eagle-import:C1206")
      (fields (field (name "MPN") "GRM31CR60J107ME39L"))
      (libsource (lib "eagle-import") (part "CERAMIC-100UF-6.3V-20%-X5R(1206)"))
    )
    (comp (ref "C28")
      (value "100u")
      (footprint "eagle-import:C1206")
      (fields (field (name "MPN") "GRM31CR60J107ME39L"))
      (libsource (lib "eagle-import") (part "CERAMIC-100UF-6.3V-20%-X5R(1206)"))
    )
    (comp (ref "C29")
      (value "100nF,")
      (footprint "eagle-import:C0805")
      (fields (field (name "MPN") "CC0805KRX7R9BB104"))
      (libsource (lib "eagle-import") (part "CERAMIC-100NF-50V-10%-X7R(0805)"))
    )
    (comp (ref "C30")
      (value "4.7u")
      (footprint "eagle-import:C0805")
      (fields (field (name "MPN") "CC0805KKX5R8BB475"))
      (libsource (lib "eagle-import") (part "CERAMIC-4.7UF-25V-10%-X5R(0805)"))
    )
    (comp (ref "C31")
      (value "100nF.")
      (footprint "eagle-import:C0805")
      (fields (field (name "MPN") "CC0805KRX7R9BB104"))
      (libsource (lib "eagle-import") (part "CERAMIC-100NF-50V-10%-X7R(0805)"))
    )
    (comp (ref "C32")
      (value "100nF.")
      (footprint "eagle-import:C0805")
      (fields (field (name "MPN") "CC0805KRX7R9BB104"))
      (libsource (lib "eagle-import") (part "CERAMIC-100NF-50V-10%-X7R(0805)"))
    )
    (comp (ref "C33")
      (value "2.2nF")
      (footprint "eagle-import:C0805")
      (fields (field (name "MPN") "CC0805KRX7R9BB104"))
      (libsource (lib "eagle-import") (part "CERAMIC-100NF-50V-10%-X7R(0805)"))
    )
    (comp (ref "C34")
      (value "100nF")
      (footprint "eagle-import:C0805")
      (fields (field (name "MPN") "CC0805KRX7R9BB104"))
      (libsource (lib "eagle-import") (part "CERAMIC-100NF-50V-10%-X7R(0805)"))
    )
    (comp (ref "C35")
      (value "100nF")
      (footprint "eagle-import:C0805")
      (fields (field (name "MPN") "CC0805KRX7R9BB104"))
      (libsource (lib "eagle-import") (part "CERAMIC-100NF-50V-10%-X7R(0805)"))
    )
    (comp (ref "C36")
      (value "100nF,")
      (footprint "eagle-import:C0805")
      (fields (field (name "MPN") "CC0805KRX7R9BB104"))
      (libsource (lib "eagle-import") (part "CERAMIC-100NF-50V-10%-X7R(0805)"))
    )
    (comp (ref "C37")
      (value "4.7u")
      (footprint "eagle-import:C0805")
      (fields (field (name "MPN") "CC0805KKX5R8BB475"))
      (libsource (lib "eagle-import") (part "CERAMIC-4.7UF-25V-10%-X5R(0805)"))
    )
    (comp (ref "C38")
      (value "10u")
      (footprint "eagle-import:C1206")
      (fields (field (name "MPN") "GRM31CR60J107ME39L"))
      (libsource (lib "eagle-import") (part "CERAMIC-100UF-6.3V-20%-X5R(1206)"))
    )
    (comp (ref "D32")
      (value "1N4007,")
      (footprint "eagle-import:DO-214AC")
      (fields (field (name "MPN") "1N4007"))
      (libsource (lib "eagle-import") (part "DIODE-GEN-PURPOSE-1KV-1A(DO-214AC)"))
    )
    (comp (ref "D33")
      (value "1N4007,")
      (footprint "eagle-import:DO-214AC")
      (fields (field (name "MPN") "1N4007"))
      (libsource (lib "eagle-import") (part "DIODE-GEN-PURPOSE-1KV-1A(DO-214AC)"))
    )
    (comp (ref "D34")
      (value "1N4007.")
      (footprint "eagle-import:DO-214AC")
      (fields (field (name "MPN") "1N4007"))
      (libsource (lib "eagle-import") (part "DIODE-GEN-PURPOSE-1KV-1A(DO-214AC)"))
    )
    (comp (ref "D35")
      (value "1N5817")
      (footprint "eagle-import:DO-214AC_SLIM")
      (libsource (lib "eagle-import") (part "DIODE-GEN-PURPOSE-1KV-1A(DO-214AC)DO-214AC/1206"))
    )
    (comp (ref "D36")
      (value "1N5817.")
      (footprint "eagle-import:DO-214AC_SLIM")
      (libsource (lib "eagle-import") (part "DIODE-GEN-PURPOSE-1KV-1A(DO-214AC)DO-214AC/1206"))
    )
    (comp (ref "D37")
      (value "1N5817.")
      (footprint "eagle-import:DO-214AC_SLIM")
      (libsource (lib "eagle-import") (part "DIODE-GEN-PURPOSE-1KV-1A(DO-214AC)DO-214AC/1206"))
    )
    (comp (ref "D38")
      (value "1N5817")
      (footprint "eagle-import:DO-214AC_SLIM")
      (libsource (lib "eagle-import") (part "DIODE-GEN-PURPOSE-1KV-1A(DO-214AC)DO-214AC/1206"))
    )
    (comp (ref "D39")
      (value "1N4007.")
      (footprint "eagle-import:DO-214AC")
      (fields (field (name "MPN") "1N4007"))
      (libsource (lib "eagle-import") (part "DIODE-GEN-PURPOSE-1KV-1A(DO-214AC)"))
    )
    (comp (ref "D40")
      (value "1N4007")
      (footprint "eagle-import:DO-214AC")
      (libsource (lib "eagle-import") (part "DIODE-GEN-PURPOSE-1KV-1A(DO-214AC)"))
    )
    (comp (ref "D41")
      (value "Zen15")
      (footprint "eagle-import:DO214AA")
      (libsource (lib "eagle-import") (part "SM6T"))
    )
    (comp (ref "D42")
      (value "SM6TDO214AA_BI")
      (footprint "eagle-import:DO214AA_BI")
      (libsource (lib "eagle-import") (part "SM6TDO214AA_BI"))
    )
    (comp (ref "D43")
      (value "SS12")
      (footprint "eagle-import:DO-214AC_SLIM")
      (libsource (lib "eagle-import") (part "DIODE-GEN-PURPOSE-1KV-1A(DO-214AC)DO-214AC/1206"))
    )
    (comp (ref "D44")
      (value "SS12")
      (footprint "eagle-import:DO-214AC_SLIM")
      (libsource (lib "eagle-import") (part "DIODE-GEN-PURPOSE-1KV-1A(DO-214AC)DO-214AC/1206"))
    )
    (comp (ref "D45")
      (value "Zen11")
      (footprint "eagle-import:SOD-123_MINI-SMA")
      (libsource (lib "eagle-import") (part "CGRM400-G1"))
    )
    (comp (ref "FID11")
      (value "FIDUCIAL")
      (footprint "eagle-import:FIDUCIAL_1MM")
      (libsource (lib "eagle-import") (part "FIDUCIAL"))
    )
    (comp (ref "FID12")
      (value "FIDUCIAL")
      (footprint "eagle-import:FIDUCIAL_1MM")
      (libsource (lib "eagle-import") (part "FIDUCIAL"))
    )
    (comp (ref "FID13")
      (value "FIDUCIAL")
      (footprint "eagle-import:FIDUCIAL_1MM")
      (libsource (lib "eagle-import") (part "FIDUCIAL"))
    )
    (comp (ref "FID14")
      (value "FIDUCIAL")
      (footprint "eagle-import:FIDUCIAL_1MM")
      (libsource (lib "eagle-import") (part "FIDUCIAL"))
    )
    (comp (ref "IC19")
      (value "4028")
      (footprint "eagle-import:SO16")
      (libsource (lib "eagle-import") (part "4028D"))
    )
    (comp (ref "IC20")
      (value "317TO202H_NOHOLE")
      (footprint "eagle-import:TO220H_NOHOLE")
      (libsource (lib "eagle-import") (part "317TO202H_NOHOLE"))
    )
    (comp (ref "IC21")
      (value "ULN2004")
      (footprint "eagle-import:SO16")
      (libsource (lib "eagle-import") (part "ULN2004AD"))
    )
    (comp (ref "IC22")
      (value "LM339")
      (footprint "eagle-import:SO14")
      (libsource (lib "eagle-import") (part "LM339D"))
    )
    (comp (ref "IC23")
      (value "78L06")
      (footprint "eagle-import:SOT89_ROUND")
      (libsource (lib "eagle-import") (part "78LXXSOT89_ROUND"))
    )
    (comp (ref "IC24")
      (value "555")
      (footprint "eagle-import:SO08")
      (libsource (lib "eagle-import") (part "555DNE"))
    )
    (comp (ref "IC25")
      (value "4538")
      (footprint "eagle-import:SO16")
      (libsource (lib "eagle-import") (part "4538D"))
    )
    (comp (ref "IC26")
      (value "78L10")
      (footprint "eagle-import:SOT89_ROUND")
      (libsource (lib "eagle-import") (part "78LXXSOT89_ROUND"))
    )
    (comp (ref "IC27")
      (value "LM2904")
      (footprint "eagle-import:SO08")
      (libsource (lib "eagle-import") (part "LM358D"))
    )
    (comp (ref "JP11")
      (value "JP2EJP2_SMALLPADS")
      (footprint "eagle-import:JP2_SMALLPADS")
      (libsource (lib "eagle-import") (part "JP2EJP2_SMALLPADS"))
    )
    (comp (ref "JP12")
      (value "JP2E_ORIG")
      (footprint "eagle-import:JP2_ORIG_SMALLPADS")
      (libsource (lib "eagle-import") (part "JP2E_ORIG"))
    )
    (comp (ref "JP13")
      (value "JP2EJP2_SMALLPADS")
      (footprint "eagle-import:JP2_SMALLPADS")
      (libsource (lib "eagle-import") (part "JP2EJP2_SMALLPADS"))
    )
    (comp (ref "JP14")
      (value "JP2EJP2_SMALLPADS")
      (footprint "eagle-import:JP2_SMALLPADS")
      (libsource (lib "eagle-import") (part "JP2EJP2_SMALLPADS"))
    )
    (comp (ref "JP15")
      (value "JP2EJP2_SMALLPADS")
      (footprint "eagle-import:JP2_SMALLPADS")
      (libsource (lib "eagle-import") (part "JP2EJP2_SMALLPADS"))
    )
    (comp (ref "LED13")
      (value "LEDLD260")
      (footprint "eagle-import:LD260")
      (libsource (lib "eagle-import") (part "LEDLD260"))
    )
    (comp (ref "LED14")
      (value "LEDLD260")
      (footprint "eagle-import:LD260")
      (libsource (lib "eagle-import") (part "LEDLD260"))
    )
    (comp (ref "LED15")
      (value "LEDLD260")
      (footprint "eagle-import:LD260")
      (libsource (lib "eagle-import") (part "LEDLD260"))
    )
    (comp (ref "LED16")
      (value "LEDLD260")
      (footprint "eagle-import:LD260")
      (libsource (lib "eagle-import") (part "LEDLD260"))
    )
    (comp (ref "LED17")
      (value "LEDLD260")
      (footprint "eagle-import:LD260")
      (libsource (lib "eagle-import") (part "LEDLD260"))
    )
    (comp (ref "LED18")
      (value "LEDLD260")
      (footprint "eagle-import:LD260")
      (libsource (lib "eagle-import") (part "LEDLD260"))
    )
    (comp (ref "Q24")
      (value "BA")
      (footprint "eagle-import:SOT89")
      (libsource (lib "eagle-import") (part "PNP-TRANSISTOR_SOT89"))
    )
    (comp (ref "Q25")
      (value "BA.")
      (footprint "eagle-import:SOT89")
      (libsource (lib "eagle-import") (part "PNP-TRANSISTOR_SOT89"))
    )
    (comp (ref "Q26")
      (value "BA.")
      (footprint "eagle-import:SOT89")
      (libsource (lib "eagle-import") (part "PNP-TRANSISTOR_SOT89"))
    )
    (comp (ref "Q27")
      (value "BA")
      (footprint "eagle-import:SOT89")
      (libsource (lib "eagle-import") (part "PNP-TRANSISTOR_SOT89"))
    )
    (comp (ref "Q28")
      (value "MY")
      (footprint "eagle-import:SOT89")
      (libsource (lib "eagle-import") (part "NPN-TRANSISTOR_SOT89"))
    )
    (comp (ref "Q29")
      (value "J1")
      (footprint "eagle-import:SOT-23")
      (fields (field (name "MPN") "BSS138W-7-F"))
      (libsource (lib "eagle-import") (part "SMD-MOSFET-N-CH-50V-200MA-BSS138W-7-F(SOT-23)"))
    )
    (comp (ref "Q30")
      (value "J1")
      (footprint "eagle-import:SOT-23")
      (fields (field (name "MPN") "BSS138W-7-F"))
      (libsource (lib "eagle-import") (part "SMD-MOSFET-N-CH-50V-200MA-BSS138W-7-F(SOT-23)"))
    )
    (comp (ref "Q31")
      (value "J1")
      (footprint "eagle-import:SOT-23")
      (fields (field (name "MPN") "BSS138W-7-F"))
      (libsource (lib "eagle-import") (part "SMD-MOSFET-N-CH-50V-200MA-BSS138W-7-F(SOT-23)"))
    )
    (comp (ref "Q32")
      (value "BA")
      (footprint "eagle-import:SOT89")
      (libsource (lib "eagle-import") (part "PNP-TRANSISTOR_SOT89"))
    )
    (comp (ref "Q33")
      (value "J1")
      (footprint "eagle-import:SOT-23")
      (fields (field (name "MPN") "BSS138W-7-F"))
      (libsource (lib "eagle-import") (part "SMD-MOSFET-N-CH-50V-200MA-BSS138W-7-F(SOT-23)"))
    )
    (comp (ref "R166")
      (value "47")
      (footprint "eagle-import:V235_17_1MM")
      (libsource (lib "eagle-import") (part "R-EU_V235/17_1MM"))
    )
    (comp (ref "R167")
      (value "13")
      (footprint "eagle-import:R1206")
      (fields (field (name "MPN") "RC1206JR-0713RL"))
      (libsource (lib "eagle-import") (part "SMD-RES-13R-5%-1/4W(1206)"))
    )
    (comp (ref "R168")
      (value "47")
      (footprint "eagle-import:V235_17_1MM")
      (libsource (lib "eagle-import") (part "R-EU_V235/17_1MM"))
    )
    (comp (ref "R169")
      (value "104")
      (footprint "eagle-import:R0805")
      (fields (field (name "MPN") "RC0805FR-0710KL"))
      (libsource (lib "eagle-import") (part "SMD-RES-10K-1%-1/8W(0805)"))
    )
    (comp (ref "R170")
      (value "104")
      (footprint "eagle-import:R0805")
      (fields (field (name "MPN") "RC0805FR-0710KL"))
      (libsource (lib "eagle-import") (part "SMD-RES-10K-1%-1/8W(0805)"))
    )
    (comp (ref "R171")
      (value "104")
      (footprint "eagle-import:R0805")
      (fields (field (name "MPN") "RC0805FR-0710KL"))
      (libsource (lib "eagle-import") (part "SMD-RES-10K-1%-1/8W(0805)"))
    )
    (comp (ref "R172")
      (value "4701")
      (footprint "eagle-import:R0805")
      (fields (field (name "MPN") "RC0805JR-074K7L"))
      (libsource (lib "eagle-import") (part "SMD-RES-4.7K-5%-1/8W(0805)"))
    )
    (comp (ref "R173")
      (value "1002")
      (footprint "eagle-import:R0805")
      (fields (field (name "MPN") "RC0805FR-0710KL"))
      (libsource (lib "eagle-import") (part "SMD-RES-10K-1%-1/8W(0805)"))
    )
    (comp (ref "R174")
      (value "1002")
      (footprint "eagle-import:R0805")
      (fields (field (name "MPN") "RC0805FR-0710KL"))
      (libsource (lib "eagle-import") (part "SMD-RES-10K-1%-1/8W(0805)"))
    )
    (comp (ref "R175")
      (value "1502")
      (footprint "eagle-import:R0805")
      (fields (field (name "MPN") "RC0805FR-0710KL"))
      (libsource (lib "eagle-import") (part "SMD-RES-10K-1%-1/8W(0805)"))
    )
    (comp (ref "R176")
      (value "104")
      (footprint "eagle-import:R0805")
      (fields (field (name "MPN") "RC0805FR-0710KL"))
      (libsource (lib "eagle-import") (part "SMD-RES-10K-1%-1/8W(0805)"))
    )
    (comp (ref "R177")
      (value "104")
      (footprint "eagle-import:R0805")
      (fields (field (name "MPN") "RC0805FR-0710KL"))
      (libsource (lib "eagle-import") (part "SMD-RES-10K-1%-1/8W(0805)"))
    )
    (comp (ref "R178")
      (value "1502")
      (footprint "eagle-import:R0805")
      (fields (field (name "MPN") "RC0805FR-0710KL"))
      (libsource (lib "eagle-import") (part "SMD-RES-10K-1%-1/8W(0805)"))
    )
    (comp (ref "R179")
      (value "1002")
      (footprint "eagle-import:R0805")
      (fields (field (name "MPN") "RC0805FR-0710KL"))
      (libsource (lib "eagle-import") (part "SMD-RES-10K-1%-1/8W(0805)"))
    )
    (comp (ref "R180")
      (value "2201")
      (footprint "eagle-import:R0805")
      (fields (field (name "MPN") "RC0805JR-072K2L"))
      (libsource (lib "eagle-import") (part "SMD-RES-2.2K-5%-1/8W(0805)"))
    )
    (comp (ref "R181")
      (value "1002")
      (footprint "eagle-import:R0805")
      (fields (field (name "MPN") "RC0805FR-0710KL"))
      (libsource (lib "eagle-import") (part "SMD-RES-10K-1%-1/8W(0805)"))
    )
    (comp (ref "R182")
      (value "4701")
      (footprint "eagle-import:R0805")
      (fields (field (name "MPN") "RC0805JR-074K7L"))
      (libsource (lib "eagle-import") (part "SMD-RES-4.7K-5%-1/8W(0805)"))
    )
    (comp (ref "R183")
      (value "2702")
      (footprint "eagle-import:R0805")
      (fields (field (name "MPN") "RC0805JR-074K7L"))
      (libsource (lib "eagle-import") (part "SMD-RES-4.7K-5%-1/8W(0805)"))
    )
    (comp (ref "R184")
      (value "102")
      (footprint "eagle-import:R0805")
      (fields (field (name "MPN") "RC0805JR-071KL"))
      (libsource (lib "eagle-import") (part "SMD-RES-1K-5%-1/8W(0805)"))
    )
    (comp (ref "R185")
      (value "R_user")
      (footprint "eagle-import:R0805")
      (libsource (lib "eagle-import") (part "R-EU_R0805"))
    )
    (comp (ref "R186")
      (value "102")
      (footprint "eagle-import:R0805")
      (fields (field (name "MPN") "RC0805JR-07220RL"))
      (libsource (lib "eagle-import") (part "SMD-RES-220R-5%-1/8W(0805)"))
    )
    (comp (ref "R187")
      (value "(101)")
      (footprint "eagle-import:R0805")
      (fields (field (name "MPN") "RC0805JR-07100RL"))
      (libsource (lib "eagle-import") (part "SMD-RES-100R-5%-1/8W(0805)"))
    )
    (comp (ref "R188")
      (value "(1000)")
      (footprint "eagle-import:R0805")
      (fields (field (name "MPN") "RC0805JR-07100RL"))
      (libsource (lib "eagle-import") (part "SMD-RES-100R-5%-1/8W(0805)"))
    )
    (comp (ref "R189")
      (value "102")
      (footprint "eagle-import:R0805")
      (fields (field (name "MPN") "RC0805JR-071KL"))
      (libsource (lib "eagle-import") (part "SMD-RES-1K-5%-1/8W(0805)"))
    )
    (comp (ref "R190")
      (value "13")
      (footprint "eagle-import:R1206")
      (fields (field (name "MPN") "RC1206JR-0713RL"))
      (libsource (lib "eagle-import") (part "SMD-RES-13R-5%-1/4W(1206)"))
    )
    (comp (ref "R191")
      (value "13")
      (footprint "eagle-import:R1206")
      (fields (field (name "MPN") "RC1206JR-0713RL"))
      (libsource (lib "eagle-import") (part "SMD-RES-13R-5%-1/4W(1206)"))
    )
    (comp (ref "R192")
      (value "2702")
      (footprint "eagle-import:R0805")
      (fields (field (name "MPN") "RC0805JR-074K7L"))
      (libsource (lib "eagle-import") (part "SMD-RES-4.7K-5%-1/8W(0805)"))
    )
    (comp (ref "R193")
      (value "4701")
      (footprint "eagle-import:R0805")
      (fields (field (name "MPN") "RC0805JR-074K7L"))
      (libsource (lib "eagle-import") (part "SMD-RES-4.7K-5%-1/8W(0805)"))
    )
    (comp (ref "R194")
      (value "100")
      (footprint "eagle-import:R0805")
      (fields (field (name "MPN") "RC0805JR-072K2L"))
      (libsource (lib "eagle-import") (part "SMD-RES-2.2K-5%-1/8W(0805)"))
    )
    (comp (ref "R195")
      (value "104")
      (footprint "eagle-import:R0805")
      (fields (field (name "MPN") "RC0805FR-0710KL"))
      (libsource (lib "eagle-import") (part "SMD-RES-10K-1%-1/8W(0805)"))
    )
    (comp (ref "R196")
      (value "104")
      (footprint "eagle-import:R0805")
      (fields (field (name "MPN") "RC0805FR-0710KL"))
      (libsource (lib "eagle-import") (part "SMD-RES-10K-1%-1/8W(0805)"))
    )
    (comp (ref "R197")
      (value "(1002)")
      (footprint "eagle-import:R0805")
      (fields (field (name "MPN") "RC0805FR-0710KL"))
      (libsource (lib "eagle-import") (part "SMD-RES-10K-1%-1/8W(0805)"))
    )
    (comp (ref "R198")
      (value "2702")
      (footprint "eagle-import:R0805")
      (fields (field (name "MPN") "RC0805FR-0710KL"))
      (libsource (lib "eagle-import") (part "SMD-RES-10K-1%-1/8W(0805)"))
    )
    (comp (ref "R199")
      (value "47")
      (footprint "eagle-import:V235_17_1MM")
      (libsource (lib "eagle-import") (part "R-EU_V235/17_1MM"))
    )
    (comp (ref "R200")
      (value "47")
      (footprint "eagle-import:V235_17_1MM")
      (libsource (lib "eagle-import") (part "R-EU_V235/17_1MM"))
    )
    (comp (ref "R201")
      (value "2702")
      (footprint "eagle-import:R0805")
      (fields (field (name "MPN") "RC0805JR-074K7L"))
      (libsource (lib "eagle-import") (part "SMD-RES-4.7K-5%-1/8W(0805)"))
    )
    (comp (ref "R202")
      (value "2201")
      (footprint "eagle-import:R0805")
      (fields (field (name "MPN") "RC0805JR-072K2L"))
      (libsource (lib "eagle-import") (part "SMD-RES-2.2K-5%-1/8W(0805)"))
    )
    (comp (ref "R203")
      (value "1002")
      (footprint "eagle-import:R0805")
      (fields (field (name "MPN") "RC0805JR-074K7L"))
      (libsource (lib "eagle-import") (part "SMD-RES-4.7K-5%-1/8W(0805)"))
    )
    (comp (ref "R204")
      (value "1002")
      (footprint "eagle-import:R0805")
      (fields (field (name "MPN") "RC0805FR-0710KL"))
      (libsource (lib "eagle-import") (part "SMD-RES-10K-1%-1/8W(0805)"))
    )
    (comp (ref "R205")
      (value "102")
      (footprint "eagle-import:R0805")
      (fields (field (name "MPN") "RC0805JR-071KL"))
      (libsource (lib "eagle-import") (part "SMD-RES-1K-5%-1/8W(0805)"))
    )
    (comp (ref "R206")
      (value "2702")
      (footprint "eagle-import:R0805")
      (fields (field (name "MPN") "RC0805JR-074K7L"))
      (libsource (lib "eagle-import") (part "SMD-RES-4.7K-5%-1/8W(0805)"))
    )
    (comp (ref "R207")
      (value "1002")
      (footprint "eagle-import:R0805")
      (fields (field (name "MPN") "RC0805JR-071KL"))
      (libsource (lib "eagle-import") (part "SMD-RES-1K-5%-1/8W(0805)"))
    )
    (comp (ref "R208")
      (value "1002")
      (footprint "eagle-import:R0805")
      (fields (field (name "MPN") "RC0805JR-071KL"))
      (libsource (lib "eagle-import") (part "SMD-RES-1K-5%-1/8W(0805)"))
    )
    (comp (ref "R209")
      (value "R_user")
      (footprint "eagle-import:R0805")
      (libsource (lib "eagle-import") (part "R-EU_R0805"))
    )
    (comp (ref "R210")
      (value "104")
      (footprint "eagle-import:R0805")
      (fields (field (name "MPN") "RC0805FR-0710KL"))
      (libsource (lib "eagle-import") (part "SMD-RES-10K-1%-1/8W(0805)"))
    )
    (comp (ref "R211")
      (value "104")
      (footprint "eagle-import:R0805")
      (fields (field (name "MPN") "RC0805FR-0710KL"))
      (libsource (lib "eagle-import") (part "SMD-RES-10K-1%-1/8W(0805)"))
    )
    (comp (ref "R212")
      (value "104")
      (footprint "eagle-import:R0805")
      (fields (field (name "MPN") "RC0805FR-0710KL"))
      (libsource (lib "eagle-import") (part "SMD-RES-10K-1%-1/8W(0805)"))
    )
    (comp (ref "R213")
      (value "13")
      (footprint "eagle-import:R1206")
      (fields (field (name "MPN") "RC1206JR-0713RL"))
      (libsource (lib "eagle-import") (part "SMD-RES-13R-5%-1/4W(1206)"))
    )
    (comp (ref "R214")
      (value "2201")
      (footprint "eagle-import:R0805")
      (fields (field (name "MPN") "RC0805JR-071KL"))
      (libsource (lib "eagle-import") (part "SMD-RES-1K-5%-1/8W(0805)"))
    )
    (comp (ref "R215")
      (value "100")
      (footprint "eagle-import:R0805")
      (fields (field (name "MPN") "RC0805JR-07220RL"))
      (libsource (lib "eagle-import") (part "SMD-RES-220R-5%-1/8W(0805)"))
    )
    (comp (ref "R216")
      (value "13")
      (footprint "eagle-import:R1206")
      (fields (field (name "MPN") "RC1206JR-0713RL"))
      (libsource (lib "eagle-import") (part "SMD-RES-13R-5%-1/4W(1206)"))
    )
    (comp (ref "R217")
      (value "4701")
      (footprint "eagle-import:R0805")
      (fields (field (name "MPN") "RC0805JR-074K7L"))
      (libsource (lib "eagle-import") (part "SMD-RES-4.7K-5%-1/8W(0805)"))
    )
    (comp (ref "R218")
      (value "104")
      (footprint "eagle-import:R0805")
      (fields (field (name "MPN") "RC0805JR-074K7L"))
      (libsource (lib "eagle-import") (part "SMD-RES-4.7K-5%-1/8W(0805)"))
    )
    (comp (ref "R219")
      (value "100")
      (footprint "eagle-import:R0805")
      (fields (field (name "MPN") "RC0805JR-072K2L"))
      (libsource (lib "eagle-import") (part "SMD-RES-2.2K-5%-1/8W(0805)"))
    )
    (comp (ref "R220")
      (value "100")
      (footprint "eagle-import:R0805")
      (fields (field (name "MPN") "RC0805JR-072K2L"))
      (libsource (lib "eagle-import") (part "SMD-RES-2.2K-5%-1/8W(0805)"))
    )
    (comp (ref "SJ3")
      (value "SJ")
      (footprint "eagle-import:SJ")
      (libsource (lib "eagle-import") (part "solder-jumper_SJ"))
    )
    (comp (ref "SJMP3")
      (value "SJ")
      (footprint "eagle-import:SJ")
      (libsource (lib "eagle-import") (part "SJ"))
    )
    (comp (ref "START3")
      (value "TPSB2.0")
      (footprint "eagle-import:B2.0")
      (libsource (lib "eagle-import") (part "TPSB2.0"))
    )
    (comp (ref "TP70")
      (value "TPSB2.0")
      (footprint "eagle-import:B2.0")
      (libsource (lib "eagle-import") (part "TPSB2.0"))
    )
    (comp (ref "TP71")
      (value "TPSB2.0")
      (footprint "eagle-import:B2.0")
      (libsource (lib "eagle-import") (part "TPSB2.0"))
    )
    (comp (ref "TP72")
      (value "TPSB2.0")
      (footprint "eagle-import:B2.0")
      (libsource (lib "eagle-import") (part "TPSB2.0"))
    )
    (comp (ref "TP73")
      (value "TPSB2.0")
      (footprint "eagle-import:B2.0")
      (libsource (lib "eagle-import") (part "TPSB2.0"))
    )
    (comp (ref "TP74")
      (value "TPSB2.0")
      (footprint "eagle-import:B2.0")
      (libsource (lib "eagle-import") (part "TPSB2.0"))
    )
    (comp (ref "TP75")
      (value "TPSB2.0")
      (footprint "eagle-import:B2.0")
      (libsource (lib "eagle-import") (part "TPSB2.0"))
    )
    (comp (ref "TP76")
      (value "TPSB2.0")
      (footprint "eagle-import:B2.0")
      (libsource (lib "eagle-import") (part "TPSB2.0"))
    )
    (comp (ref "TP77")
      (value "TPSB2.0")
      (footprint "eagle-import:B2.0")
      (libsource (lib "eagle-import") (part "TPSB2.0"))
    )
    (comp (ref "TP78")
      (value "TPSB2.0")
      (footprint "eagle-import:B2.0")
      (libsource (lib "eagle-import") (part "TPSB2.0"))
    )
    (comp (ref "TP79")
      (value "TPSB2.0")
      (footprint "eagle-import:B2.0")
      (libsource (lib "eagle-import") (part "TPSB2.0"))
    )
    (comp (ref "TP80")
      (value "TPSB2.0")
      (footprint "eagle-import:B2.0")
      (libsource (lib "eagle-import") (part "TPSB2.0"))
    )
    (comp (ref "TP81")
      (value "TPSB2.0")
      (footprint "eagle-import:B2.0")
      (libsource (lib "eagle-import") (part "TPSB2.0"))
    )
    (comp (ref "TP82")
      (value "TPSB2.0")
      (footprint "eagle-import:B2.0")
      (libsource (lib "eagle-import") (part "TPSB2.0"))
    )
    (comp (ref "TP83")
      (value "TPSB2.0")
      (footprint "eagle-import:B2.0")
      (libsource (lib "eagle-import") (part "TPSB2.0"))
    )
    (comp (ref "TP84")
      (value "TPSB2.0")
      (footprint "eagle-import:B2.0")
      (libsource (lib "eagle-import") (part "TPSB2.0"))
    )
    (comp (ref "TP85")
      (value "TPSB2.0")
      (footprint "eagle-import:B2.0")
      (libsource (lib "eagle-import") (part "TPSB2.0"))
    )
    (comp (ref "TP86")
      (value "TPSB2.0")
      (footprint "eagle-import:B2.0")
      (libsource (lib "eagle-import") (part "TPSB2.0"))
    )
    (comp (ref "TP87")
      (value "TPSB2.0")
      (footprint "eagle-import:B2.0")
      (libsource (lib "eagle-import") (part "TPSB2.0"))
    )
    (comp (ref "TP88")
      (value "TPSB1,27")
      (footprint "eagle-import:B1,27")
      (libsource (lib "eagle-import") (part "TPSB1,27"))
    )
    (comp (ref "TP89")
      (value "TPSB2.0")
      (footprint "eagle-import:B2.0")
      (libsource (lib "eagle-import") (part "TPSB2.0"))
    )
    (comp (ref "TP90")
      (value "TPSB2.0")
      (footprint "eagle-import:B2.0")
      (libsource (lib "eagle-import") (part "TPSB2.0"))
    )
    (comp (ref "TP91")
      (value "TPSB2.0")
      (footprint "eagle-import:B2.0")
      (libsource (lib "eagle-import") (part "TPSB2.0"))
    )
    (comp (ref "TP92")
      (value "TPSB2.0")
      (footprint "eagle-import:B2.0")
      (libsource (lib "eagle-import") (part "TPSB2.0"))
    )
    (comp (ref "X7")
      (value "CON_BMWV2")
      (footprint "eagle-import:24-PIN_V2")
      (libsource (lib "eagle-import") (part "CON_BMWV2"))
    )
    (comp (ref "X8")
      (value "22-23-2051")
      (footprint "eagle-import:22-23-2051")
      (fields (field (name "MF") "MOLEX"))
      (libsource (lib "eagle-import") (part "22-23-2051"))
    )
    (comp (ref "X9")
      (value "22-23-2021")
      (footprint "eagle-import:22-23-2021")
      (fields (field (name "MF") "MOLEX"))
      (libsource (lib "eagle-import") (part "22-23-2021"))
    )
  )
  (nets
    (net (code "1") (name "+10V") (class "Default")
      (node (ref "10V") (pin "TP") (pinfunction "PP_TP") (pintype "input"))
      (node (ref "10V3") (pin "TP") (pinfunction "PP_TP") (pintype "input"))
      (node (ref "C102") (pin "1") (pinfunction "1_1") (pintype "passive"))
      (node (ref "C34") (pin "1") (pinfunction "1_1") (pintype "passive"))
      (node (ref "IC104") (pin "1") (pinfunction "OUT_1") (pintype "passive"))
      (node (ref "IC110") (pin "4") (pinfunction "R_4") (pintype "input"))
      (node (ref "IC110") (pin "8") (pinfunction "V+_8") (pintype "power_in"))
      (node (ref "IC111") (pin "13") (pinfunction "CD_13") (pintype "input"))
      (node (ref "IC111") (pin "16") (pinfunction "VDD_16") (pintype "power_in"))
      (node (ref "IC111") (pin "3") (pinfunction "CD_3") (pintype "input"))
      (node (ref "IC111") (pin "5") (pinfunction "B_5") (pintype "input"))
      (node (ref "IC24") (pin "4") (pinfunction "R_4") (pintype "input"))
      (node (ref "IC24") (pin "8") (pinfunction "V+_8") (pintype "power_in"))
      (node (ref "IC25") (pin "13") (pinfunction "CD_13") (pintype "input"))
      (node (ref "IC25") (pin "16") (pinfunction "VDD_16") (pintype "power_in"))
      (node (ref "IC25") (pin "3") (pinfunction "CD_3") (pintype "input"))
      (node (ref "IC25") (pin "5") (pinfunction "B_5") (pintype "input"))
      (node (ref "IC26") (pin "1") (pinfunction "OUT_1") (pintype "passive"))
      (node (ref "R10") (pin "2") (pinfunction "2_2") (pintype "passive"))
      (node (ref "R145") (pin "2") (pinfunction "2_2") (pintype "passive"))
      (node (ref "R201") (pin "2") (pinfunction "2_2") (pintype "passive"))
      (node (ref "R218") (pin "2") (pinfunction "2_2") (pintype "passive"))
    )
    (net (code "2") (name "+12V") (class "Default")
      (node (ref "2") (pin "1") (pinfunction "KL_1") (pintype "passive"))
      (node (ref "8") (pin "1") (pinfunction "KL_1") (pintype "passive"))
      (node (ref "C2") (pin "1") (pinfunction "1_1") (pintype "passive"))
      (node (ref "C38") (pin "1") (pinfunction "1_1") (pintype "passive"))
      (node (ref "D101") (pin "C") (pinfunction "C_C") (pintype "passive"))
      (node (ref "D41") (pin "C") (pinfunction "C_C") (pintype "passive"))
      (node (ref "IC102") (pin "3") (pinfunction "IN_3") (pintype "input"))
      (node (ref "IC104") (pin "3") (pinfunction "IN_3") (pintype "input"))
      (node (ref "IC105") (pin "16") (pinfunction "VDD_16") (pintype "power_in"))
      (node (ref "IC107") (pin "9") (pinfunction "CD+_9") (pintype "passive"))
      (node (ref "IC19") (pin "16") (pinfunction "VDD_16") (pintype "power_in"))
      (node (ref "IC21") (pin "9") (pinfunction "CD+_9") (pintype "passive"))
      (node (ref "IC23") (pin "3") (pinfunction "IN_3") (pintype "input"))
      (node (ref "IC26") (pin "3") (pinfunction "IN_3") (pintype "input"))
      (node (ref "JP101") (pin "2") (pinfunction "2_2") (pintype "passive"))
      (node (ref "JP11") (pin "2") (pinfunction "2_2") (pintype "passive"))
      (node (ref "R102") (pin "1") (pinfunction "1_1") (pintype "passive"))
      (node (ref "R106") (pin "1") (pinfunction "1_1") (pintype "passive"))
      (node (ref "R109") (pin "2") (pinfunction "2_2") (pintype "passive"))
      (node (ref "R110") (pin "2") (pinfunction "2_2") (pintype "passive"))
      (node (ref "R111") (pin "2") (pinfunction "2_2") (pintype "passive"))
      (node (ref "R12") (pin "2") (pinfunction "2_2") (pintype "passive"))
      (node (ref "R13") (pin "2") (pinfunction "2_2") (pintype "passive"))
      (node (ref "R135") (pin "1") (pinfunction "1_1") (pintype "passive"))
      (node (ref "R169") (pin "2") (pinfunction "2_2") (pintype "passive"))
      (node (ref "R170") (pin "2") (pinfunction "2_2") (pintype "passive"))
      (node (ref "R171") (pin "2") (pinfunction "2_2") (pintype "passive"))
      (node (ref "R190") (pin "1") (pinfunction "1_1") (pintype "passive"))
      (node (ref "R191") (pin "1") (pinfunction "1_1") (pintype "passive"))
      (node (ref "R195") (pin "1") (pinfunction "1_1") (pintype "passive"))
      (node (ref "R219") (pin "2") (pinfunction "2_2") (pintype "passive"))
      (node (ref "R220") (pin "2") (pinfunction "2_2") (pintype "passive"))
      (node (ref "TP12") (pin "TP") (pinfunction "PP_TP") (pintype "input"))
      (node (ref "TP91") (pin "TP") (pinfunction "PP_TP") (pintype "input"))
      (node (ref "X103") (pin "1") (pinfunction "S_1") (pintype "passive"))
      (node (ref "X8") (pin "1") (pinfunction "S_1") (pintype "passive"))
    )
    (net (code "3") (name "GND") (class "Default")
      (node (ref "1") (pin "12") (pinfunction "KL_12") (pintype "passive"))
      (node (ref "7") (pin "12") (pinfunction "KL_12") (pintype "passive"))
      (node (ref "C101") (pin "2") (pinfunction "2_2") (pintype "passive"))
      (node (ref "C102") (pin "2") (pinfunction "2_2") (pintype "passive"))
      (node (ref "C103") (pin "2") (pinfunction "2_2") (pintype "passive"))
      (node (ref "C104") (pin "2") (pinfunction "2_2") (pintype "passive"))
      (node (ref "C105") (pin "2") (pinfunction "2_2") (pintype "passive"))
      (node (ref "C106") (pin "1") (pinfunction "1_1") (pintype "passive"))
      (node (ref "C107") (pin "2") (pinfunction "2_2") (pintype "passive"))
      (node (ref "C108") (pin "2") (pinfunction "2_2") (pintype "passive"))
      (node (ref "C109") (pin "1") (pinfunction "1_1") (pintype "passive"))
      (node (ref "C110") (pin "2") (pinfunction "2_2") (pintype "passive"))
      (node (ref "C15") (pin "1") (pinfunction "1_1") (pintype "passive"))
      (node (ref "C2") (pin "2") (pinfunction "2_2") (pintype "passive"))
      (node (ref "C27") (pin "2") (pinfunction "2_2") (pintype "passive"))
      (node (ref "C28") (pin "2") (pinfunction "2_2") (pintype "passive"))
      (node (ref "C29") (pin "2") (pinfunction "2_2") (pintype "passive"))
      (node (ref "C30") (pin "2") (pinfunction "2_2") (pintype "passive"))
      (node (ref "C31") (pin "2") (pinfunction "2_2") (pintype "passive"))
      (node (ref "C32") (pin "1") (pinfunction "1_1") (pintype "passive"))
      (node (ref "C33") (pin "1") (pinfunction "1_1") (pintype "passive"))
      (node (ref "C34") (pin "2") (pinfunction "2_2") (pintype "passive"))
      (node (ref "C35") (pin "2") (pinfunction "2_2") (pintype "passive"))
      (node (ref "C36") (pin "2") (pinfunction "2_2") (pintype "passive"))
      (node (ref "C37") (pin "1") (pinfunction "1_1") (pintype "passive"))
      (node (ref "C38") (pin "2") (pinfunction "2_2") (pintype "passive"))
      (node (ref "D101") (pin "A") (pinfunction "A_A") (pintype "passive"))
      (node (ref "D104") (pin "A") (pinfunction "A_A") (pintype "passive"))
      (node (ref "D105") (pin "1") (pinfunction "+_1") (pintype "passive"))
      (node (ref "D39") (pin "1") (pinfunction "+_1") (pintype "passive"))
      (node (ref "D4") (pin "A") (pinfunction "A_A") (pintype "passive"))
      (node (ref "D41") (pin "A") (pinfunction "A_A") (pintype "passive"))
      (node (ref "D42") (pin "A") (pinfunction "A_A") (pintype "passive"))
      (node (ref "D45") (pin "A") (pinfunction "A_A") (pintype "passive"))
      (node (ref "IC101") (pin "4") (pinfunction "V-_4") (pintype "power_in"))
      (node (ref "IC102") (pin "2") (pinfunction "GND_2") (pintype "input"))
      (node (ref "IC102") (pin "2@1") (pinfunction "GND_2@1") (pintype "input"))
      (node (ref "IC104") (pin "2") (pinfunction "GND_2") (pintype "input"))
      (node (ref "IC104") (pin "2@1") (pinfunction "GND_2@1") (pintype "input"))
      (node (ref "IC105") (pin "11") (pinfunction "D_11") (pintype "input"))
      (node (ref "IC105") (pin "8") (pinfunction "VSS_8") (pintype "power_in"))
      (node (ref "IC107") (pin "8") (pinfunction "GND_8") (pintype "power_in"))
      (node (ref "IC108") (pin "12") (pinfunction "GND_12") (pintype "power_in"))
      (node (ref "IC110") (pin "1") (pinfunction "GND_1") (pintype "power_in"))
      (node (ref "IC111") (pin "1") (pinfunction "T1_1") (pintype "input"))
      (node (ref "IC111") (pin "15") (pinfunction "T1_15") (pintype "input"))
      (node (ref "IC111") (pin "8") (pinfunction "VSS_8") (pintype "power_in"))
      (node (ref "IC19") (pin "11") (pinfunction "D_11") (pintype "input"))
      (node (ref "IC19") (pin "8") (pinfunction "VSS_8") (pintype "power_in"))
      (node (ref "IC21") (pin "8") (pinfunction "GND_8") (pintype "power_in"))
      (node (ref "IC22") (pin "12") (pinfunction "GND_12") (pintype "power_in"))
      (node (ref "IC23") (pin "2") (pinfunction "GND_2") (pintype "input"))
      (node (ref "IC23") (pin "2@1") (pinfunction "GND_2@1") (pintype "input"))
      (node (ref "IC24") (pin "1") (pinfunction "GND_1") (pintype "power_in"))
      (node (ref "IC25") (pin "1") (pinfunction "T1_1") (pintype "input"))
      (node (ref "IC25") (pin "15") (pinfunction "T1_15") (pintype "input"))
      (node (ref "IC25") (pin "8") (pinfunction "VSS_8") (pintype "power_in"))
      (node (ref "IC26") (pin "2") (pinfunction "GND_2") (pintype "input"))
      (node (ref "IC26") (pin "2@1") (pinfunction "GND_2@1") (pintype "input"))
      (node (ref "IC27") (pin "4") (pinfunction "V-_4") (pintype "power_in"))
      (node (ref "Q1") (pin "2") (pinfunction "S_2") (pintype "passive"))
      (node (ref "Q107") (pin "2") (pinfunction "S_2") (pintype "passive"))
      (node (ref "Q29") (pin "2") (pinfunction "S_2") (pintype "passive"))
      (node (ref "Q3") (pin "2") (pinfunction "S_2") (pintype "passive"))
      (node (ref "Q31") (pin "2") (pinfunction "S_2") (pintype "passive"))
      (node (ref "Q33") (pin "2") (pinfunction "S_2") (pintype "passive"))
      (node (ref "R101") (pin "2") (pinfunction "2_2") (pintype "passive"))
      (node (ref "R103") (pin "2") (pinfunction "2_2") (pintype "passive"))
      (node (ref "R104") (pin "2") (pinfunction "2_2") (pintype "passive"))
      (node (ref "R107") (pin "1") (pinfunction "1_1") (pintype "passive"))
      (node (ref "R114") (pin "1") (pinfunction "1_1") (pintype "passive"))
      (node (ref "R123") (pin "1") (pinfunction "1_1") (pintype "passive"))
      (node (ref "R132") (pin "1") (pinfunction "1_1") (pintype "passive"))
      (node (ref "R136") (pin "1") (pinfunction "1_1") (pintype "passive"))
      (node (ref "R137") (pin "1") (pinfunction "1_1") (pintype "passive"))
      (node (ref "R141") (pin "2") (pinfunction "2_2") (pintype "passive"))
      (node (ref "R143") (pin "2") (pinfunction "2_2") (pintype "passive"))
      (node (ref "R173") (pin "1") (pinfunction "1_1") (pintype "passive"))
      (node (ref "R179") (pin "1") (pinfunction "1_1") (pintype "passive"))
      (node (ref "R183") (pin "1") (pinfunction "1_1") (pintype "passive"))
      (node (ref "R184") (pin "2") (pinfunction "2_2") (pintype "passive"))
      (node (ref "R185") (pin "2") (pinfunction "2_2") (pintype "passive"))
      (node (ref "R187") (pin "2") (pinfunction "2_2") (pintype "passive"))
      (node (ref "R196") (pin "2") (pinfunction "2_2") (pintype "passive"))
      (node (ref "R199") (pin "1") (pinfunction "1_1") (pintype "passive"))
      (node (ref "R200") (pin "1") (pinfunction "1_1") (pintype "passive"))
      (node (ref "R208") (pin "1") (pinfunction "1_1") (pintype "passive"))
      (node (ref "R209") (pin "2") (pinfunction "2_2") (pintype "passive"))
      (node (ref "R213") (pin "2") (pinfunction "2_2") (pintype "passive"))
      (node (ref "R214") (pin "2") (pinfunction "2_2") (pintype "passive"))
      (node (ref "R215") (pin "1") (pinfunction "1_1") (pintype "passive"))
      (node (ref "R4") (pin "1") (pinfunction "1_1") (pintype "passive"))
      (node (ref "R5") (pin "2") (pinfunction "2_2") (pintype "passive"))
      (node (ref "R6") (pin "2") (pinfunction "2_2") (pintype "passive"))
      (node (ref "X101") (pin "13") (pinfunction "13_13") (pintype "passive"))
      (node (ref "X101") (pin "18") (pinfunction "18_18") (pintype "passive"))
      (node (ref "X101") (pin "23") (pinfunction "23_23") (pintype "passive"))
      (node (ref "X102") (pin "1") (pinfunction "S_1") (pintype "passive"))
      (node (ref "X103") (pin "5") (pinfunction "S_5") (pintype "passive"))
      (node (ref "X7") (pin "13") (pinfunction "13_13") (pintype "passive"))
      (node (ref "X7") (pin "18") (pinfunction "18_18") (pintype "passive"))
      (node (ref "X7") (pin "23") (pinfunction "23_23") (pintype "passive"))
      (node (ref "X8") (pin "5") (pinfunction "S_5") (pintype "passive"))
      (node (ref "X9") (pin "1") (pinfunction "S_1") (pintype "passive"))
    )
    (net (code "4") (name "Net-(1A-KL)") (class "Default")
      (node (ref "1") (pin "1") (pinfunction "KL_1") (pintype "passive"))
      (node (ref "D2") (pin "2") (pinfunction "-_2") (pintype "passive"))
      (node (ref "TP1") (pin "TP") (pinfunction "PP_TP") (pintype "input"))
    )
    (net (code "5") (name "Net-(1B-KL)") (class "Default")
      (node (ref "1") (pin "10") (pinfunction "KL_10") (pintype "passive"))
      (node (ref "D102") (pin "2") (pinfunction "-_2") (pintype "passive"))
      (node (ref "D103") (pin "2") (pinfunction "-_2") (pintype "passive"))
      (node (ref "JP104") (pin "1") (pinfunction "1_1") (pintype "passive"))
      (node (ref "SJ101") (pin "1") (pinfunction "1_1") (pintype "passive"))
      (node (ref "TP10") (pin "TP") (pinfunction "PP_TP") (pintype "input"))
    )
    (net (code "6") (name "Net-(1C-KL)") (class "Default")
      (node (ref "1") (pin "11") (pinfunction "KL_11") (pintype "passive"))
      (node (ref "D103") (pin "1") (pinfunction "+_1") (pintype "passive"))
      (node (ref "TP11") (pin "TP") (pinfunction "PP_TP") (pintype "input"))
      (node (ref "X101") (pin "19") (pinfunction "19_19") (pintype "passive"))
    )
    (net (code "7") (name "Net-(1E-KL)") (class "Default")
      (node (ref "1") (pin "2") (pinfunction "KL_2") (pintype "passive"))
      (node (ref "Q101") (pin "2") (pinfunction "C_2") (pintype "passive"))
      (node (ref "TP2") (pin "TP") (pinfunction "PP_TP") (pintype "input"))
    )
    (net (code "8") (name "Net-(1F-KL)") (class "Default")
      (node (ref "1") (pin "3") (pinfunction "KL_3") (pintype "passive"))
      (node (ref "IC107") (pin "11") (pinfunction "O6_11") (pintype "open_collector"))
      (node (ref "TP3") (pin "TP") (pinfunction "PP_TP") (pintype "input"))
    )
    (net (code "9") (name "Net-(1G-KL)") (class "Default")
      (node (ref "1") (pin "4") (pinfunction "KL_4") (pintype "passive"))
      (node (ref "IC107") (pin "10") (pinfunction "O7_10") (pintype "open_collector"))
      (node (ref "TP4") (pin "TP") (pinfunction "PP_TP") (pintype "input"))
    )
    (net (code "10") (name "Net-(1H-KL)") (class "Default")
      (node (ref "1") (pin "5") (pinfunction "KL_5") (pintype "passive"))
      (node (ref "IC107") (pin "12") (pinfunction "O5_12") (pintype "open_collector"))
      (node (ref "TP5") (pin "TP") (pinfunction "PP_TP") (pintype "input"))
    )
    (net (code "11") (name "Net-(1I-KL)") (class "Default")
      (node (ref "1") (pin "6") (pinfunction "KL_6") (pintype "passive"))
      (node (ref "IC107") (pin "13") (pinfunction "O4_13") (pintype "open_collector"))
      (node (ref "TP6") (pin "TP") (pinfunction "PP_TP") (pintype "input"))
    )
    (net (code "12") (name "Net-(1J-KL)") (class "Default")
      (node (ref "1") (pin "7") (pinfunction "KL_7") (pintype "passive"))
      (node (ref "IC107") (pin "14") (pinfunction "O3_14") (pintype "open_collector"))
      (node (ref "TP7") (pin "TP") (pinfunction "PP_TP") (pintype "input"))
    )
    (net (code "13") (name "Net-(1K-KL)") (class "Default")
      (node (ref "1") (pin "8") (pinfunction "KL_8") (pintype "passive"))
      (node (ref "R9") (pin "2") (pinfunction "2_2") (pintype "passive"))
      (node (ref "TP8") (pin "TP") (pinfunction "PP_TP") (pintype "input"))
    )
    (net (code "14") (name "Net-(1L-KL)") (class "Default")
      (node (ref "1") (pin "9") (pinfunction "KL_9") (pintype "passive"))
      (node (ref "D102") (pin "1") (pinfunction "+_1") (pintype "passive"))
      (node (ref "TP9") (pin "TP") (pinfunction "PP_TP") (pintype "input"))
      (node (ref "X101") (pin "17") (pinfunction "17_17") (pintype "passive"))
    )
    (net (code "15") (name "Net-(2B-KL)") (class "Default")
      (node (ref "2") (pin "10") (pinfunction "KL_10") (pintype "passive"))
      (node (ref "TP25") (pin "TP") (pinfunction "PP_TP") (pintype "input"))
      (node (ref "X101") (pin "15") (pinfunction "15_15") (pintype "passive"))
    )
    (net (code "16") (name "Net-(2C-KL)") (class "Default")
      (node (ref "2") (pin "11") (pinfunction "KL_11") (pintype "passive"))
      (node (ref "Q103") (pin "2") (pinfunction "C_2") (pintype "passive"))
      (node (ref "R119") (pin "1") (pinfunction "1_1") (pintype "passive"))
      (node (ref "TP26") (pin "TP") (pinfunction "PP_TP") (pintype "input"))
    )
    (net (code "17") (name "Net-(2D-KL)") (class "Default")
      (node (ref "2") (pin "12") (pinfunction "KL_12") (pintype "passive"))
      (node (ref "R146") (pin "1") (pinfunction "1_1") (pintype "passive"))
      (node (ref "TP13") (pin "TP") (pinfunction "PP_TP") (pintype "input"))
    )
    (net (code "18") (name "Net-(2E-KL)") (class "Default")
      (node (ref "2") (pin "2") (pinfunction "KL_2") (pintype "passive"))
      (node (ref "D109") (pin "2") (pinfunction "-_2") (pintype "passive"))
      (node (ref "LED102") (pin "K") (pinfunction "C_K") (pintype "passive"))
      (node (ref "TP16") (pin "TP") (pinfunction "PP_TP") (pintype "input"))
      (node (ref "X101") (pin "12") (pinfunction "12_12") (pintype "passive"))
    )
    (net (code "19") (name "Net-(2F-KL)") (class "Default")
      (node (ref "2") (pin "3") (pinfunction "KL_3") (pintype "passive"))
      (node (ref "D108") (pin "2") (pinfunction "-_2") (pintype "passive"))
      (node (ref "LED103") (pin "K") (pinfunction "C_K") (pintype "passive"))
      (node (ref "TP17") (pin "TP") (pinfunction "PP_TP") (pintype "input"))
      (node (ref "X101") (pin "11") (pinfunction "11_11") (pintype "passive"))
    )
    (net (code "20") (name "Net-(2G-KL)") (class "Default")
      (node (ref "2") (pin "4") (pinfunction "KL_4") (pintype "passive"))
      (node (ref "D107") (pin "2") (pinfunction "-_2") (pintype "passive"))
      (node (ref "LED104") (pin "K") (pinfunction "C_K") (pintype "passive"))
      (node (ref "TP18") (pin "TP") (pinfunction "PP_TP") (pintype "input"))
      (node (ref "X101") (pin "10") (pinfunction "10_10") (pintype "passive"))
    )
    (net (code "21") (name "Net-(2H-KL)") (class "Default")
      (node (ref "2") (pin "5") (pinfunction "KL_5") (pintype "passive"))
      (node (ref "D106") (pin "2") (pinfunction "-_2") (pintype "passive"))
      (node (ref "LED105") (pin "K") (pinfunction "C_K") (pintype "passive"))
      (node (ref "TP19") (pin "TP") (pinfunction "PP_TP") (pintype "input"))
      (node (ref "X101") (pin "9") (pinfunction "9_9") (pintype "passive"))
    )
    (net (code "22") (name "Net-(2I-KL)") (class "Default")
      (node (ref "2") (pin "6") (pinfunction "KL_6") (pintype "passive"))
      (node (ref "JP105") (pin "2") (pinfunction "2_2") (pintype "passive"))
      (node (ref "TP21") (pin "TP") (pinfunction "PP_TP") (pintype "input"))
    )
    (net (code "23") (name "Net-(2J-KL)") (class "Default")
      (node (ref "2") (pin "7") (pinfunction "KL_7") (pintype "passive"))
      (node (ref "LED101") (pin "A") (pinfunction "A_A") (pintype "passive"))
      (node (ref "TP22") (pin "TP") (pinfunction "PP_TP") (pintype "input"))
      (node (ref "X101") (pin "8") (pinfunction "8_8") (pintype "passive"))
    )
    (net (code "24") (name "Net-(2K-KL)") (class "Default")
      (node (ref "2") (pin "8") (pinfunction "KL_8") (pintype "passive"))
      (node (ref "D110") (pin "2") (pinfunction "-_2") (pintype "passive"))
      (node (ref "LED106") (pin "K") (pinfunction "C_K") (pintype "passive"))
      (node (ref "TP23") (pin "TP") (pinfunction "PP_TP") (pintype "input"))
      (node (ref "X101") (pin "14") (pinfunction "14_14") (pintype "passive"))
    )
    (net (code "25") (name "Net-(2L-KL)") (class "Default")
      (node (ref "2") (pin "9") (pinfunction "KL_9") (pintype "passive"))
      (node (ref "D107") (pin "1") (pinfunction "+_1") (pintype "passive"))
      (node (ref "D108") (pin "1") (pinfunction "+_1") (pintype "passive"))
      (node (ref "JP102") (pin "1") (pinfunction "1_1") (pintype "passive"))
      (node (ref "JP103") (pin "2") (pinfunction "2_2") (pintype "passive"))
      (node (ref "TP24") (pin "TP") (pinfunction "PP_TP") (pintype "input"))
    )
    (net (code "26") (name "Net-(7A-KL)") (class "Default")
      (node (ref "7") (pin "1") (pinfunction "KL_1") (pintype "passive"))
      (node (ref "D44") (pin "2") (pinfunction "-_2") (pintype "passive"))
      (node (ref "TP70") (pin "TP") (pinfunction "PP_TP") (pintype "input"))
    )
    (net (code "27") (name "Net-(7B-KL)") (class "Default")
      (node (ref "7") (pin "10") (pinfunction "KL_10") (pintype "passive"))
      (node (ref "D32") (pin "2") (pinfunction "-_2") (pintype "passive"))
      (node (ref "D33") (pin "2") (pinfunction "-_2") (pintype "passive"))
      (node (ref "JP15") (pin "1") (pinfunction "1_1") (pintype "passive"))
      (node (ref "SJ3") (pin "1") (pinfunction "1_1") (pintype "passive"))
      (node (ref "TP79") (pin "TP") (pinfunction "PP_TP") (pintype "input"))
    )
    (net (code "28") (name "Net-(7C-KL)") (class "Default")
      (node (ref "7") (pin "11") (pinfunction "KL_11") (pintype "passive"))
      (node (ref "D33") (pin "1") (pinfunction "+_1") (pintype "passive"))
      (node (ref "TP80") (pin "TP") (pinfunction "PP_TP") (pintype "input"))
      (node (ref "X7") (pin "19") (pinfunction "19_19") (pintype "passive"))
    )
    (net (code "29") (name "Net-(7E-KL)") (class "Default")
      (node (ref "7") (pin "2") (pinfunction "KL_2") (pintype "passive"))
      (node (ref "Q26") (pin "2") (pinfunction "C_2") (pintype "passive"))
      (node (ref "TP71") (pin "TP") (pinfunction "PP_TP") (pintype "input"))
    )
    (net (code "30") (name "Net-(7F-KL)") (class "Default")
      (node (ref "7") (pin "3") (pinfunction "KL_3") (pintype "passive"))
      (node (ref "IC21") (pin "11") (pinfunction "O6_11") (pintype "open_collector"))
      (node (ref "TP72") (pin "TP") (pinfunction "PP_TP") (pintype "input"))
    )
    (net (code "31") (name "Net-(7G-KL)") (class "Default")
      (node (ref "7") (pin "4") (pinfunction "KL_4") (pintype "passive"))
      (node (ref "IC21") (pin "10") (pinfunction "O7_10") (pintype "open_collector"))
      (node (ref "TP73") (pin "TP") (pinfunction "PP_TP") (pintype "input"))
    )
    (net (code "32") (name "Net-(7H-KL)") (class "Default")
      (node (ref "7") (pin "5") (pinfunction "KL_5") (pintype "passive"))
      (node (ref "IC21") (pin "12") (pinfunction "O5_12") (pintype "open_collector"))
      (node (ref "TP74") (pin "TP") (pinfunction "PP_TP") (pintype "input"))
    )
    (net (code "33") (name "Net-(7I-KL)") (class "Default")
      (node (ref "7") (pin "6") (pinfunction "KL_6") (pintype "passive"))
      (node (ref "IC21") (pin "13") (pinfunction "O4_13") (pintype "open_collector"))
      (node (ref "TP75") (pin "TP") (pinfunction "PP_TP") (pintype "input"))
    )
    (net (code "34") (name "Net-(7J-KL)") (class "Default")
      (node (ref "7") (pin "7") (pinfunction "KL_7") (pintype "passive"))
      (node (ref "IC21") (pin "14") (pinfunction "O3_14") (pintype "open_collector"))
      (node (ref "TP76") (pin "TP") (pinfunction "PP_TP") (pintype "input"))
    )
    (net (code "35") (name "Net-(7K-KL)") (class "Default")
      (node (ref "7") (pin "8") (pinfunction "KL_8") (pintype "passive"))
      (node (ref "R216") (pin "2") (pinfunction "2_2") (pintype "passive"))
      (node (ref "TP77") (pin "TP") (pinfunction "PP_TP") (pintype "input"))
    )
    (net (code "36") (name "Net-(7L-KL)") (class "Default")
      (node (ref "7") (pin "9") (pinfunction "KL_9") (pintype "passive"))
      (node (ref "D32") (pin "1") (pinfunction "+_1") (pintype "passive"))
      (node (ref "TP78") (pin "TP") (pinfunction "PP_TP") (pintype "input"))
      (node (ref "X7") (pin "17") (pinfunction "17_17") (pintype "passive"))
    )
    (net (code "37") (name "Net-(8B-KL)") (class "Default")
      (node (ref "8") (pin "10") (pinfunction "KL_10") (pintype "passive"))
      (node (ref "TP89") (pin "TP") (pinfunction "PP_TP") (pintype "input"))
      (node (ref "X7") (pin "15") (pinfunction "15_15") (pintype "passive"))
    )
    (net (code "38") (name "Net-(8C-KL)") (class "Default")
      (node (ref "8") (pin "11") (pinfunction "KL_11") (pintype "passive"))
      (node (ref "Q28") (pin "2") (pinfunction "C_2") (pintype "passive"))
      (node (ref "R202") (pin "1") (pinfunction "1_1") (pintype "passive"))
      (node (ref "TP90") (pin "TP") (pinfunction "PP_TP") (pintype "input"))
    )
    (net (code "39") (name "Net-(8D-KL)") (class "Default")
      (node (ref "8") (pin "12") (pinfunction "KL_12") (pintype "passive"))
      (node (ref "R203") (pin "1") (pinfunction "1_1") (pintype "passive"))
      (node (ref "TP92") (pin "TP") (pinfunction "PP_TP") (pintype "input"))
    )
    (net (code "40") (name "Net-(8E-KL)") (class "Default")
      (node (ref "8") (pin "2") (pinfunction "KL_2") (pintype "passive"))
      (node (ref "D37") (pin "2") (pinfunction "-_2") (pintype "passive"))
      (node (ref "LED13") (pin "K") (pinfunction "C_K") (pintype "passive"))
      (node (ref "TP81") (pin "TP") (pinfunction "PP_TP") (pintype "input"))
      (node (ref "X7") (pin "12") (pinfunction "12_12") (pintype "passive"))
    )
    (net (code "41") (name "Net-(8F-KL)") (class "Default")
      (node (ref "8") (pin "3") (pinfunction "KL_3") (pintype "passive"))
      (node (ref "D36") (pin "2") (pinfunction "-_2") (pintype "passive"))
      (node (ref "LED14") (pin "K") (pinfunction "C_K") (pintype "passive"))
      (node (ref "TP82") (pin "TP") (pinfunction "PP_TP") (pintype "input"))
      (node (ref "X7") (pin "11") (pinfunction "11_11") (pintype "passive"))
    )
    (net (code "42") (name "Net-(8G-KL)") (class "Default")
      (node (ref "8") (pin "4") (pinfunction "KL_4") (pintype "passive"))
      (node (ref "D35") (pin "2") (pinfunction "-_2") (pintype "passive"))
      (node (ref "LED15") (pin "K") (pinfunction "C_K") (pintype "passive"))
      (node (ref "TP83") (pin "TP") (pinfunction "PP_TP") (pintype "input"))
      (node (ref "X7") (pin "10") (pinfunction "10_10") (pintype "passive"))
    )
    (net (code "43") (name "Net-(8H-KL)") (class "Default")
      (node (ref "8") (pin "5") (pinfunction "KL_5") (pintype "passive"))
      (node (ref "D34") (pin "2") (pinfunction "-_2") (pintype "passive"))
      (node (ref "LED16") (pin "K") (pinfunction "C_K") (pintype "passive"))
      (node (ref "TP84") (pin "TP") (pinfunction "PP_TP") (pintype "input"))
      (node (ref "X7") (pin "9") (pinfunction "9_9") (pintype "passive"))
    )
    (net (code "44") (name "Net-(8I-KL)") (class "Default")
      (node (ref "8") (pin "6") (pinfunction "KL_6") (pintype "passive"))
      (node (ref "JP12") (pin "2") (pinfunction "2_2") (pintype "passive"))
      (node (ref "TP85") (pin "TP") (pinfunction "PP_TP") (pintype "input"))
    )
    (net (code "45") (name "Net-(8J-KL)") (class "Default")
      (node (ref "8") (pin "7") (pinfunction "KL_7") (pintype "passive"))
      (node (ref "LED17") (pin "A") (pinfunction "A_A") (pintype "passive"))
      (node (ref "TP86") (pin "TP") (pinfunction "PP_TP") (pintype "input"))
      (node (ref "X7") (pin "8") (pinfunction "8_8") (pintype "passive"))
    )
    (net (code "46") (name "Net-(8K-KL)") (class "Default")
      (node (ref "8") (pin "8") (pinfunction "KL_8") (pintype "passive"))
      (node (ref "D38") (pin "2") (pinfunction "-_2") (pintype "passive"))
      (node (ref "LED18") (pin "K") (pinfunction "C_K") (pintype "passive"))
      (node (ref "TP87") (pin "TP") (pinfunction "PP_TP") (pintype "input"))
      (node (ref "X7") (pin "14") (pinfunction "14_14") (pintype "passive"))
    )
    (net (code "47") (name "Net-(8L-KL)") (class "Default")
      (node (ref "8") (pin "9") (pinfunction "KL_9") (pintype "passive"))
      (node (ref "D35") (pin "1") (pinfunction "+_1") (pintype "passive"))
      (node (ref "D36") (pin "1") (pinfunction "+_1") (pintype "passive"))
      (node (ref "JP13") (pin "1") (pinfunction "1_1") (pintype "passive"))
      (node (ref "JP14") (pin "2") (pinfunction "2_2") (pintype "passive"))
      (node (ref "TP88") (pin "TP") (pinfunction "PP_TP") (pintype "input"))
    )
    (net (code "48") (name "Net-(C27-Pad1)") (class "Default")
      (node (ref "C27") (pin "1") (pinfunction "1_1") (pintype "passive"))
      (node (ref "R176") (pin "1") (pinfunction "1_1") (pintype "passive"))
      (node (ref "R177") (pin "2") (pinfunction "2_2") (pintype "passive"))
    )
    (net (code "49") (name "Net-(C36-Pad1)") (class "Default")
      (node (ref "C36") (pin "1") (pinfunction "1_1") (pintype "passive"))
      (node (ref "R204") (pin "1") (pinfunction "1_1") (pintype "passive"))
      (node (ref "R205") (pin "1") (pinfunction "1_1") (pintype "passive"))
    )
    (net (code "50") (name "Net-(C103-Pad1)") (class "Default")
      (node (ref "C103") (pin "1") (pinfunction "1_1") (pintype "passive"))
      (node (ref "R108") (pin "1") (pinfunction "1_1") (pintype "passive"))
      (node (ref "R112") (pin "1") (pinfunction "1_1") (pintype "passive"))
    )
    (net (code "51") (name "Net-(C107-Pad1)") (class "Default")
      (node (ref "C107") (pin "1") (pinfunction "1_1") (pintype "passive"))
      (node (ref "R125") (pin "1") (pinfunction "1_1") (pintype "passive"))
      (node (ref "R130") (pin "2") (pinfunction "2_2") (pintype "passive"))
    )
    (net (code "52") (name "Net-(D1--)") (class "Default")
      (node (ref "D1") (pin "2") (pinfunction "-_2") (pintype "passive"))
      (node (ref "Q104") (pin "3") (pinfunction "E_3") (pintype "passive"))
      (node (ref "R12") (pin "1") (pinfunction "1_1") (pintype "passive"))
      (node (ref "R13") (pin "1") (pinfunction "1_1") (pintype "passive"))
    )
    (net (code "53") (name "Net-(D2-+)") (class "Default")
      (node (ref "D2") (pin "1") (pinfunction "+_1") (pintype "passive"))
      (node (ref "X101") (pin "1") (pinfunction "1_1") (pintype "passive"))
    )
    (net (code "54") (name "Net-(D34-+)") (class "Default")
      (node (ref "D34") (pin "1") (pinfunction "+_1") (pintype "passive"))
      (node (ref "R166") (pin "1") (pinfunction "1_1") (pintype "passive"))
    )
    (net (code "55") (name "Net-(D37-+)") (class "Default")
      (node (ref "D37") (pin "1") (pinfunction "+_1") (pintype "passive"))
      (node (ref "JP13") (pin "2") (pinfunction "2_2") (pintype "passive"))
    )
    (net (code "56") (name "Net-(D38-+)") (class "Default")
      (node (ref "D38") (pin "1") (pinfunction "+_1") (pintype "passive"))
      (node (ref "JP14") (pin "1") (pinfunction "1_1") (pintype "passive"))
    )
    (net (code "57") (name "Net-(D39--)") (class "Default")
      (node (ref "D39") (pin "2") (pinfunction "-_2") (pintype "passive"))
      (node (ref "Q24") (pin "2") (pinfunction "C_2") (pintype "passive"))
      (node (ref "START3") (pin "TP") (pinfunction "PP_TP") (pintype "input"))
      (node (ref "X7") (pin "5") (pinfunction "5_5") (pintype "passive"))
    )
    (net (code "58") (name "Net-(D40-+)") (class "Default")
      (node (ref "D40") (pin "1") (pinfunction "+_1") (pintype "passive"))
      (node (ref "R198") (pin "1") (pinfunction "1_1") (pintype "passive"))
    )
    (net (code "59") (name "Net-(D40--)") (class "Default")
      (node (ref "C33") (pin "2") (pinfunction "2_2") (pintype "passive"))
      (node (ref "D40") (pin "2") (pinfunction "-_2") (pintype "passive"))
      (node (ref "D45") (pin "C") (pinfunction "C_C") (pintype "passive"))
      (node (ref "IC24") (pin "2") (pinfunction "TR_2") (pintype "input"))
      (node (ref "IC24") (pin "6") (pinfunction "THR_6") (pintype "input"))
      (node (ref "R196") (pin "1") (pinfunction "1_1") (pintype "passive"))
    )
    (net (code "60") (name "Net-(D42-PadC)") (class "Default")
      (node (ref "D42") (pin "C") (pinfunction "C_C") (pintype "passive"))
      (node (ref "R172") (pin "2") (pinfunction "2_2") (pintype "passive"))
      (node (ref "X7") (pin "22") (pinfunction "22_22") (pintype "passive"))
    )
    (net (code "61") (name "Net-(D43--)") (class "Default")
      (node (ref "D43") (pin "2") (pinfunction "-_2") (pintype "passive"))
      (node (ref "R219") (pin "1") (pinfunction "1_1") (pintype "passive"))
      (node (ref "R220") (pin "1") (pinfunction "1_1") (pintype "passive"))
    )
    (net (code "62") (name "Net-(D44-+)") (class "Default")
      (node (ref "D44") (pin "1") (pinfunction "+_1") (pintype "passive"))
      (node (ref "X7") (pin "1") (pinfunction "1_1") (pintype "passive"))
    )
    (net (code "63") (name "Net-(D104-PadC)") (class "Default")
      (node (ref "D104") (pin "C") (pinfunction "C_C") (pintype "passive"))
      (node (ref "R105") (pin "2") (pinfunction "2_2") (pintype "passive"))
      (node (ref "X101") (pin "22") (pinfunction "22_22") (pintype "passive"))
    )
    (net (code "64") (name "Net-(D105--)") (class "Default")
      (node (ref "D105") (pin "2") (pinfunction "-_2") (pintype "passive"))
      (node (ref "Q104") (pin "2") (pinfunction "C_2") (pintype "passive"))
      (node (ref "START") (pin "TP") (pinfunction "PP_TP") (pintype "input"))
      (node (ref "X101") (pin "5") (pinfunction "5_5") (pintype "passive"))
    )
    (net (code "65") (name "Net-(D106-+)") (class "Default")
      (node (ref "D106") (pin "1") (pinfunction "+_1") (pintype "passive"))
      (node (ref "R127") (pin "1") (pinfunction "1_1") (pintype "passive"))
    )
    (net (code "66") (name "Net-(D109-+)") (class "Default")
      (node (ref "D109") (pin "1") (pinfunction "+_1") (pintype "passive"))
      (node (ref "JP102") (pin "2") (pinfunction "2_2") (pintype "passive"))
    )
    (net (code "67") (name "Net-(D110-+)") (class "Default")
      (node (ref "D110") (pin "1") (pinfunction "+_1") (pintype "passive"))
      (node (ref "JP103") (pin "1") (pinfunction "1_1") (pintype "passive"))
    )
    (net (code "68") (name "Net-(D112-+)") (class "Default")
      (node (ref "D112") (pin "1") (pinfunction "+_1") (pintype "passive"))
      (node (ref "R140") (pin "1") (pinfunction "1_1") (pintype "passive"))
    )
    (net (code "69") (name "Net-(D112--)") (class "Default")
      (node (ref "C109") (pin "2") (pinfunction "2_2") (pintype "passive"))
      (node (ref "D112") (pin "2") (pinfunction "-_2") (pintype "passive"))
      (node (ref "D4") (pin "C") (pinfunction "C_C") (pintype "passive"))
      (node (ref "IC110") (pin "2") (pinfunction "TR_2") (pintype "input"))
      (node (ref "IC110") (pin "6") (pinfunction "THR_6") (pintype "input"))
      (node (ref "R141") (pin "1") (pinfunction "1_1") (pintype "passive"))
    )
    (net (code "70") (name "Net-(IC19A-A)") (class "Default")
      (node (ref "IC19") (pin "10") (pinfunction "A_10") (pintype "input"))
      (node (ref "R171") (pin "1") (pinfunction "1_1") (pintype "passive"))
      (node (ref "R212") (pin "1") (pinfunction "1_1") (pintype "passive"))
      (node (ref "R212") (pin "2") (pinfunction "2_2") (pintype "passive"))
      (node (ref "X7") (pin "4") (pinfunction "4_4") (pintype "passive"))
      (node (ref "X8") (pin "2") (pinfunction "S_2") (pintype "passive"))
    )
    (net (code "71") (name "Net-(IC19A-B)") (class "Default")
      (node (ref "IC19") (pin "13") (pinfunction "B_13") (pintype "input"))
      (node (ref "R170") (pin "1") (pinfunction "1_1") (pintype "passive"))
      (node (ref "R211") (pin "1") (pinfunction "1_1") (pintype "passive"))
      (node (ref "R211") (pin "2") (pinfunction "2_2") (pintype "passive"))
      (node (ref "X7") (pin "3") (pinfunction "3_3") (pintype "passive"))
      (node (ref "X8") (pin "3") (pinfunction "S_3") (pintype "passive"))
    )
    (net (code "72") (name "Net-(IC19A-C)") (class "Default")
      (node (ref "IC19") (pin "12") (pinfunction "C_12") (pintype "input"))
      (node (ref "R169") (pin "1") (pinfunction "1_1") (pintype "passive"))
      (node (ref "R210") (pin "1") (pinfunction "1_1") (pintype "passive"))
      (node (ref "R210") (pin "2") (pinfunction "2_2") (pintype "passive"))
      (node (ref "X7") (pin "2") (pinfunction "2_2") (pintype "passive"))
      (node (ref "X8") (pin "4") (pinfunction "S_4") (pintype "passive"))
    )
    (net (code "73") (name "Net-(IC19A-Q0)") (class "Default")
      (node (ref "IC19") (pin "3") (pinfunction "Q0_3") (pintype "output"))
      (node (ref "IC21") (pin "1") (pinfunction "I1_1") (pintype "input"))
      (node (ref "IC21") (pin "2") (pinfunction "I2_2") (pintype "input"))
      (node (ref "Q30") (pin "1") (pinfunction "G_1") (pintype "passive"))
      (node (ref "Q31") (pin "1") (pinfunction "G_1") (pintype "passive"))
    )
    (net (code "74") (name "Net-(IC19A-Q1)") (class "Default")
      (node (ref "IC19") (pin "14") (pinfunction "Q1_14") (pintype "output"))
      (node (ref "IC21") (pin "6") (pinfunction "I6_6") (pintype "input"))
    )
    (net (code "75") (name "Net-(IC19A-Q2)") (class "Default")
      (node (ref "IC19") (pin "2") (pinfunction "Q2_2") (pintype "output"))
      (node (ref "IC21") (pin "7") (pinfunction "I7_7") (pintype "input"))
    )
    (net (code "76") (name "Net-(IC19A-Q3)") (class "Default")
      (node (ref "IC19") (pin "15") (pinfunction "Q3_15") (pintype "output"))
      (node (ref "IC21") (pin "5") (pinfunction "I5_5") (pintype "input"))
    )
    (net (code "77") (name "Net-(IC19A-Q4)") (class "Default")
      (node (ref "IC19") (pin "1") (pinfunction "Q4_1") (pintype "output"))
      (node (ref "IC21") (pin "4") (pinfunction "I4_4") (pintype "input"))
    )
    (net (code "78") (name "Net-(IC19A-Q5)") (class "Default")
      (node (ref "IC19") (pin "6") (pinfunction "Q5_6") (pintype "output"))
      (node (ref "IC21") (pin "3") (pinfunction "I3_3") (pintype "input"))
    )
    (net (code "79") (name "Net-(IC20-ADJ)") (class "Default")
      (node (ref "IC20") (pin "1") (pinfunction "ADJ_1") (pintype "input"))
      (node (ref "R167") (pin "1") (pinfunction "1_1") (pintype "passive"))
      (node (ref "R174") (pin "2") (pinfunction "2_2") (pintype "passive"))
      (node (ref "X7") (pin "7") (pinfunction "7_7") (pintype "passive"))
    )
    (net (code "80") (name "Net-(IC20-VI)") (class "Default")
      (node (ref "IC20") (pin "3") (pinfunction "VI_3") (pintype "input"))
      (node (ref "Q27") (pin "2") (pinfunction "C_2") (pintype "passive"))
    )
    (net (code "81") (name "Net-(IC20-VO)") (class "Default")
      (node (ref "IC20") (pin "2") (pinfunction "VO_2") (pintype "passive"))
      (node (ref "R167") (pin "2") (pinfunction "2_2") (pintype "passive"))
    )
    (net (code "82") (name "Net-(IC21-O1)") (class "Default")
      (node (ref "IC21") (pin "16") (pinfunction "O1_16") (pintype "open_collector"))
      (node (ref "Q30") (pin "3") (pinfunction "D_3") (pintype "passive"))
      (node (ref "R216") (pin "1") (pinfunction "1_1") (pintype "passive"))
    )
    (net (code "83") (name "Net-(IC21-O2)") (class "Default")
      (node (ref "IC21") (pin "15") (pinfunction "O2_15") (pintype "open_collector"))
      (node (ref "R189") (pin "1") (pinfunction "1_1") (pintype "passive"))
    )
    (net (code "84") (name "Net-(IC22A-+IN)") (class "Default")
      (node (ref "IC22") (pin "11") (pinfunction "+IN_11") (pintype "input"))
      (node (ref "IC22") (pin "5") (pinfunction "+IN_5") (pintype "input"))
      (node (ref "R178") (pin "1") (pinfunction "1_1") (pintype "passive"))
      (node (ref "R179") (pin "2") (pinfunction "2_2") (pintype "passive"))
      (node (ref "R180") (pin "2") (pinfunction "2_2") (pintype "passive"))
    )
    (net (code "85") (name "Net-(IC22A--IN)") (class "Default")
      (node (ref "C28") (pin "1") (pinfunction "1_1") (pintype "passive"))
      (node (ref "IC22") (pin "10") (pinfunction "-IN_10") (pintype "input"))
      (node (ref "IC22") (pin "4") (pinfunction "-IN_4") (pintype "input"))
      (node (ref "R177") (pin "1") (pinfunction "1_1") (pintype "passive"))
    )
    (net (code "86") (name "Net-(IC22A-OUT)") (class "Default")
      (node (ref "IC22") (pin "2") (pinfunction "OUT_2") (pintype "open_collector"))
      (node (ref "R180") (pin "1") (pinfunction "1_1") (pintype "passive"))
    )
    (net (code "87") (name "Net-(IC22B-+IN)") (class "Default")
      (node (ref "IC22") (pin "7") (pinfunction "+IN_7") (pintype "input"))
      (node (ref "R175") (pin "1") (pinfunction "1_1") (pintype "passive"))
      (node (ref "R192") (pin "1") (pinfunction "1_1") (pintype "passive"))
    )
    (net (code "88") (name "Net-(IC22B--IN)") (class "Default")
      (node (ref "IC22") (pin "6") (pinfunction "-IN_6") (pintype "input"))
      (node (ref "IC22") (pin "8") (pinfunction "-IN_8") (pintype "input"))
      (node (ref "R174") (pin "1") (pinfunction "1_1") (pintype "passive"))
    )
    (net (code "89") (name "Net-(IC22B-OUT)") (class "Default")
      (node (ref "IC22") (pin "1") (pinfunction "OUT_1") (pintype "open_collector"))
      (node (ref "R176") (pin "2") (pinfunction "2_2") (pintype "passive"))
      (node (ref "R181") (pin "2") (pinfunction "2_2") (pintype "passive"))
    )
    (net (code "90") (name "Net-(IC22C-+IN)") (class "Default")
      (node (ref "C31") (pin "1") (pinfunction "1_1") (pintype "passive"))
      (node (ref "IC22") (pin "9") (pinfunction "+IN_9") (pintype "input"))
      (node (ref "R183") (pin "2") (pinfunction "2_2") (pintype "passive"))
      (node (ref "R192") (pin "2") (pinfunction "2_2") (pintype "passive"))
    )
    (net (code "91") (name "Net-(IC22C-OUT)") (class "Default")
      (node (ref "C32") (pin "2") (pinfunction "2_2") (pintype "passive"))
      (node (ref "IC22") (pin "14") (pinfunction "OUT_14") (pintype "open_collector"))
      (node (ref "R182") (pin "2") (pinfunction "2_2") (pintype "passive"))
    )
    (net (code "92") (name "Net-(IC22D-OUT)") (class "Default")
      (node (ref "IC22") (pin "13") (pinfunction "OUT_13") (pintype "open_collector"))
      (node (ref "JP12") (pin "1") (pinfunction "1_1") (pintype "passive"))
      (node (ref "Q29") (pin "1") (pinfunction "G_1") (pintype "passive"))
      (node (ref "R195") (pin "2") (pinfunction "2_2") (pintype "passive"))
    )
    (net (code "93") (name "Net-(IC24-CV)") (class "Default")
      (node (ref "IC24") (pin "5") (pinfunction "CV_5") (pintype "input"))
      (node (ref "R197") (pin "2") (pinfunction "2_2") (pintype "passive"))
    )
    (net (code "94") (name "Net-(IC24-Q)") (class "Default")
      (node (ref "IC24") (pin "3") (pinfunction "Q_3") (pintype "output"))
      (node (ref "IC25") (pin "12") (pinfunction "A_12") (pintype "input"))
      (node (ref "IC25") (pin "4") (pinfunction "A_4") (pintype "input"))
      (node (ref "R197") (pin "1") (pinfunction "1_1") (pintype "passive"))
    )
    (net (code "95") (name "Net-(IC25A-Q)") (class "Default")
      (node (ref "IC25") (pin "6") (pinfunction "Q_6") (pintype "output"))
      (node (ref "Q33") (pin "1") (pinfunction "G_1") (pintype "passive"))
    )
    (net (code "96") (name "Net-(IC25A-T2)") (class "Default")
      (node (ref "C37") (pin "2") (pinfunction "2_2") (pintype "passive"))
      (node (ref "IC25") (pin "2") (pinfunction "T2_2") (pintype "input"))
      (node (ref "R218") (pin "1") (pinfunction "1_1") (pintype "passive"))
    )
    (net (code "97") (name "Net-(IC25B-B)") (class "Default")
      (node (ref "IC25") (pin "11") (pinfunction "B_11") (pintype "input"))
      (node (ref "IC25") (pin "9") (pinfunction "~{Q}_9") (pintype "output"))
      (node (ref "R203") (pin "2") (pinfunction "2_2") (pintype "passive"))
    )
    (net (code "98") (name "Net-(IC25B-T2)") (class "Default")
      (node (ref "C35") (pin "1") (pinfunction "1_1") (pintype "passive"))
      (node (ref "IC25") (pin "14") (pinfunction "T2_14") (pintype "input"))
      (node (ref "R201") (pin "1") (pinfunction "1_1") (pintype "passive"))
    )
    (net (code "99") (name "Net-(IC27A-+IN)") (class "Default")
      (node (ref "C30") (pin "1") (pinfunction "1_1") (pintype "passive"))
      (node (ref "IC27") (pin "3") (pinfunction "+IN_3") (pintype "input"))
      (node (ref "R172") (pin "1") (pinfunction "1_1") (pintype "passive"))
    )
    (net (code "100") (name "Net-(IC27A--IN)") (class "Default")
      (node (ref "IC27") (pin "2") (pinfunction "-IN_2") (pintype "input"))
      (node (ref "R173") (pin "2") (pinfunction "2_2") (pintype "passive"))
    )
    (net (code "101") (name "Net-(IC27A-OUT)") (class "Default")
      (node (ref "IC27") (pin "1") (pinfunction "OUT_1") (pintype "output"))
      (node (ref "R204") (pin "2") (pinfunction "2_2") (pintype "passive"))
    )
    (net (code "102") (name "Net-(IC27B-+IN)") (class "Default")
      (node (ref "IC27") (pin "5") (pinfunction "+IN_5") (pintype "input"))
      (node (ref "Q31") (pin "3") (pinfunction "D_3") (pintype "passive"))
      (node (ref "R205") (pin "2") (pinfunction "2_2") (pintype "passive"))
      (node (ref "R206") (pin "2") (pinfunction "2_2") (pintype "passive"))
    )
    (net (code "103") (name "Net-(IC27B--IN)") (class "Default")
      (node (ref "IC27") (pin "6") (pinfunction "-IN_6") (pintype "input"))
      (node (ref "R207") (pin "1") (pinfunction "1_1") (pintype "passive"))
      (node (ref "R208") (pin "2") (pinfunction "2_2") (pintype "passive"))
    )
    (net (code "104") (name "Net-(IC27B-OUT)") (class "Default")
      (node (ref "IC27") (pin "7") (pinfunction "OUT_7") (pintype "output"))
      (node (ref "R186") (pin "2") (pinfunction "2_2") (pintype "passive"))
      (node (ref "R193") (pin "1") (pinfunction "1_1") (pintype "passive"))
      (node (ref "R206") (pin "1") (pinfunction "1_1") (pintype "passive"))
    )
    (net (code "105") (name "Net-(IC101A-+IN)") (class "Default")
      (node (ref "C101") (pin "1") (pinfunction "1_1") (pintype "passive"))
      (node (ref "IC101") (pin "3") (pinfunction "+IN_3") (pintype "input"))
      (node (ref "R105") (pin "1") (pinfunction "1_1") (pintype "passive"))
    )
    (net (code "106") (name "Net-(IC101A--IN)") (class "Default")
      (node (ref "IC101") (pin "2") (pinfunction "-IN_2") (pintype "input"))
      (node (ref "R107") (pin "2") (pinfunction "2_2") (pintype "passive"))
    )
    (net (code "107") (name "Net-(IC101A-OUT)") (class "Default")
      (node (ref "IC101") (pin "1") (pinfunction "OUT_1") (pintype "output"))
      (node (ref "R108") (pin "2") (pinfunction "2_2") (pintype "passive"))
    )
    (net (code "108") (name "Net-(IC101B-+IN)") (class "Default")
      (node (ref "IC101") (pin "5") (pinfunction "+IN_5") (pintype "input"))
      (node (ref "Q1") (pin "3") (pinfunction "D_3") (pintype "passive"))
      (node (ref "R112") (pin "2") (pinfunction "2_2") (pintype "passive"))
      (node (ref "R117") (pin "2") (pinfunction "2_2") (pintype "passive"))
    )
    (net (code "109") (name "Net-(IC101B--IN)") (class "Default")
      (node (ref "IC101") (pin "6") (pinfunction "-IN_6") (pintype "input"))
      (node (ref "R113") (pin "1") (pinfunction "1_1") (pintype "passive"))
      (node (ref "R114") (pin "2") (pinfunction "2_2") (pintype "passive"))
    )
    (net (code "110") (name "Net-(IC101B-OUT)") (class "Default")
      (node (ref "IC101") (pin "7") (pinfunction "OUT_7") (pintype "output"))
      (node (ref "R115") (pin "2") (pinfunction "2_2") (pintype "passive"))
      (node (ref "R116") (pin "1") (pinfunction "1_1") (pintype "passive"))
      (node (ref "R117") (pin "1") (pinfunction "1_1") (pintype "passive"))
    )
    (net (code "111") (name "Net-(IC105A-A)") (class "Default")
      (node (ref "IC105") (pin "10") (pinfunction "A_10") (pintype "input"))
      (node (ref "R111") (pin "1") (pinfunction "1_1") (pintype "passive"))
      (node (ref "R3") (pin "1") (pinfunction "1_1") (pintype "passive"))
      (node (ref "R3") (pin "2") (pinfunction "2_2") (pintype "passive"))
      (node (ref "X101") (pin "4") (pinfunction "4_4") (pintype "passive"))
      (node (ref "X103") (pin "2") (pinfunction "S_2") (pintype "passive"))
    )
    (net (code "112") (name "Net-(IC105A-B)") (class "Default")
      (node (ref "IC105") (pin "13") (pinfunction "B_13") (pintype "input"))
      (node (ref "R110") (pin "1") (pinfunction "1_1") (pintype "passive"))
      (node (ref "R2") (pin "1") (pinfunction "1_1") (pintype "passive"))
      (node (ref "R2") (pin "2") (pinfunction "2_2") (pintype "passive"))
      (node (ref "X101") (pin "3") (pinfunction "3_3") (pintype "passive"))
      (node (ref "X103") (pin "3") (pinfunction "S_3") (pintype "passive"))
    )
    (net (code "113") (name "Net-(IC105A-C)") (class "Default")
      (node (ref "IC105") (pin "12") (pinfunction "C_12") (pintype "input"))
      (node (ref "R1") (pin "1") (pinfunction "1_1") (pintype "passive"))
      (node (ref "R1") (pin "2") (pinfunction "2_2") (pintype "passive"))
      (node (ref "R109") (pin "1") (pinfunction "1_1") (pintype "passive"))
      (node (ref "X101") (pin "2") (pinfunction "2_2") (pintype "passive"))
      (node (ref "X103") (pin "4") (pinfunction "S_4") (pintype "passive"))
    )
    (net (code "114") (name "Net-(IC105A-Q0)") (class "Default")
      (node (ref "IC105") (pin "3") (pinfunction "Q0_3") (pintype "output"))
      (node (ref "IC107") (pin "1") (pinfunction "I1_1") (pintype "input"))
      (node (ref "IC107") (pin "2") (pinfunction "I2_2") (pintype "input"))
      (node (ref "Q1") (pin "1") (pinfunction "G_1") (pintype "passive"))
      (node (ref "Q106") (pin "1") (pinfunction "G_1") (pintype "passive"))
    )
    (net (code "115") (name "Net-(IC105A-Q1)") (class "Default")
      (node (ref "IC105") (pin "14") (pinfunction "Q1_14") (pintype "output"))
      (node (ref "IC107") (pin "6") (pinfunction "I6_6") (pintype "input"))
    )
    (net (code "116") (name "Net-(IC105A-Q2)") (class "Default")
      (node (ref "IC105") (pin "2") (pinfunction "Q2_2") (pintype "output"))
      (node (ref "IC107") (pin "7") (pinfunction "I7_7") (pintype "input"))
    )
    (net (code "117") (name "Net-(IC105A-Q3)") (class "Default")
      (node (ref "IC105") (pin "15") (pinfunction "Q3_15") (pintype "output"))
      (node (ref "IC107") (pin "5") (pinfunction "I5_5") (pintype "input"))
    )
    (net (code "118") (name "Net-(IC105A-Q4)") (class "Default")
      (node (ref "IC105") (pin "1") (pinfunction "Q4_1") (pintype "output"))
      (node (ref "IC107") (pin "4") (pinfunction "I4_4") (pintype "input"))
    )
    (net (code "119") (name "Net-(IC105A-Q5)") (class "Default")
      (node (ref "IC105") (pin "6") (pinfunction "Q5_6") (pintype "output"))
      (node (ref "IC107") (pin "3") (pinfunction "I3_3") (pintype "input"))
    )
    (net (code "120") (name "Net-(IC107-O1)") (class "Default")
      (node (ref "IC107") (pin "16") (pinfunction "O1_16") (pintype "open_collector"))
      (node (ref "Q106") (pin "3") (pinfunction "D_3") (pintype "passive"))
      (node (ref "R9") (pin "1") (pinfunction "1_1") (pintype "passive"))
    )
    (net (code "121") (name "Net-(IC107-O2)") (class "Default")
      (node (ref "IC107") (pin "15") (pinfunction "O2_15") (pintype "open_collector"))
      (node (ref "R128") (pin "1") (pinfunction "1_1") (pintype "passive"))
    )
    (net (code "122") (name "Net-(IC108A-+IN)") (class "Default")
      (node (ref "IC108") (pin "11") (pinfunction "+IN_11") (pintype "input"))
      (node (ref "IC108") (pin "5") (pinfunction "+IN_5") (pintype "input"))
      (node (ref "R131") (pin "1") (pinfunction "1_1") (pintype "passive"))
      (node (ref "R132") (pin "2") (pinfunction "2_2") (pintype "passive"))
      (node (ref "R133") (pin "2") (pinfunction "2_2") (pintype "passive"))
    )
    (net (code "123") (name "Net-(IC108A--IN)") (class "Default")
      (node (ref "C108") (pin "1") (pinfunction "1_1") (pintype "passive"))
      (node (ref "IC108") (pin "10") (pinfunction "-IN_10") (pintype "input"))
      (node (ref "IC108") (pin "4") (pinfunction "-IN_4") (pintype "input"))
      (node (ref "R130") (pin "1") (pinfunction "1_1") (pintype "passive"))
    )
    (net (code "124") (name "Net-(IC108A-OUT)") (class "Default")
      (node (ref "IC108") (pin "2") (pinfunction "OUT_2") (pintype "open_collector"))
      (node (ref "R133") (pin "1") (pinfunction "1_1") (pintype "passive"))
    )
    (net (code "125") (name "Net-(IC108B-+IN)") (class "Default")
      (node (ref "IC108") (pin "7") (pinfunction "+IN_7") (pintype "input"))
      (node (ref "R121") (pin "1") (pinfunction "1_1") (pintype "passive"))
      (node (ref "R122") (pin "1") (pinfunction "1_1") (pintype "passive"))
    )
    (net (code "126") (name "Net-(IC108B--IN)") (class "Default")
      (node (ref "IC108") (pin "6") (pinfunction "-IN_6") (pintype "input"))
      (node (ref "IC108") (pin "8") (pinfunction "-IN_8") (pintype "input"))
      (node (ref "R120") (pin "1") (pinfunction "1_1") (pintype "passive"))
    )
    (net (code "127") (name "Net-(IC108B-OUT)") (class "Default")
      (node (ref "IC108") (pin "1") (pinfunction "OUT_1") (pintype "open_collector"))
      (node (ref "R124") (pin "2") (pinfunction "2_2") (pintype "passive"))
      (node (ref "R125") (pin "2") (pinfunction "2_2") (pintype "passive"))
    )
    (net (code "128") (name "Net-(IC108C-+IN)") (class "Default")
      (node (ref "C105") (pin "1") (pinfunction "1_1") (pintype "passive"))
      (node (ref "IC108") (pin "9") (pinfunction "+IN_9") (pintype "input"))
      (node (ref "R122") (pin "2") (pinfunction "2_2") (pintype "passive"))
      (node (ref "R123") (pin "2") (pinfunction "2_2") (pintype "passive"))
    )
    (net (code "129") (name "Net-(IC108C-OUT)") (class "Default")
      (node (ref "C106") (pin "2") (pinfunction "2_2") (pintype "passive"))
      (node (ref "IC108") (pin "14") (pinfunction "OUT_14") (pintype "open_collector"))
      (node (ref "R126") (pin "2") (pinfunction "2_2") (pintype "passive"))
    )
    (net (code "130") (name "Net-(IC108D-OUT)") (class "Default")
      (node (ref "IC108") (pin "13") (pinfunction "OUT_13") (pintype "open_collector"))
      (node (ref "JP105") (pin "1") (pinfunction "1_1") (pintype "passive"))
      (node (ref "Q107") (pin "1") (pinfunction "G_1") (pintype "passive"))
      (node (ref "R135") (pin "2") (pinfunction "2_2") (pintype "passive"))
    )
    (net (code "131") (name "Net-(IC109-ADJ)") (class "Default")
      (node (ref "IC109") (pin "1") (pinfunction "ADJ_1") (pintype "input"))
      (node (ref "R120") (pin "2") (pinfunction "2_2") (pintype "passive"))
      (node (ref "R134") (pin "1") (pinfunction "1_1") (pintype "passive"))
      (node (ref "X101") (pin "7") (pinfunction "7_7") (pintype "passive"))
    )
    (net (code "132") (name "Net-(IC109-VI)") (class "Default")
      (node (ref "IC109") (pin "3") (pinfunction "VI_3") (pintype "input"))
      (node (ref "Q105") (pin "2") (pinfunction "C_2") (pintype "passive"))
    )
    (net (code "133") (name "Net-(IC109-VO)") (class "Default")
      (node (ref "IC109") (pin "2") (pinfunction "VO_2") (pintype "passive"))
      (node (ref "R134") (pin "2") (pinfunction "2_2") (pintype "passive"))
    )
    (net (code "134") (name "Net-(IC110-CV)") (class "Default")
      (node (ref "IC110") (pin "5") (pinfunction "CV_5") (pintype "input"))
      (node (ref "R144") (pin "2") (pinfunction "2_2") (pintype "passive"))
    )
    (net (code "135") (name "Net-(IC110-Q)") (class "Default")
      (node (ref "IC110") (pin "3") (pinfunction "Q_3") (pintype "output"))
      (node (ref "IC111") (pin "12") (pinfunction "A_12") (pintype "input"))
      (node (ref "IC111") (pin "4") (pinfunction "A_4") (pintype "input"))
      (node (ref "R144") (pin "1") (pinfunction "1_1") (pintype "passive"))
    )
    (net (code "136") (name "Net-(IC111A-Q)") (class "Default")
      (node (ref "IC111") (pin "6") (pinfunction "Q_6") (pintype "output"))
      (node (ref "Q3") (pin "1") (pinfunction "G_1") (pintype "passive"))
    )
    (net (code "137") (name "Net-(IC111A-T2)") (class "Default")
      (node (ref "C15") (pin "2") (pinfunction "2_2") (pintype "passive"))
      (node (ref "IC111") (pin "2") (pinfunction "T2_2") (pintype "input"))
      (node (ref "R10") (pin "1") (pinfunction "1_1") (pintype "passive"))
    )
    (net (code "138") (name "Net-(IC111B-B)") (class "Default")
      (node (ref "IC111") (pin "11") (pinfunction "B_11") (pintype "input"))
      (node (ref "IC111") (pin "9") (pinfunction "~{Q}_9") (pintype "output"))
      (node (ref "R146") (pin "2") (pinfunction "2_2") (pintype "passive"))
    )
    (net (code "139") (name "Net-(IC111B-T2)") (class "Default")
      (node (ref "C110") (pin "1") (pinfunction "1_1") (pintype "passive"))
      (node (ref "IC111") (pin "14") (pinfunction "T2_14") (pintype "input"))
      (node (ref "R145") (pin "1") (pinfunction "1_1") (pintype "passive"))
    )
    (net (code "140") (name "Net-(JP11-Pad1)") (class "Default")
      (node (ref "JP11") (pin "1") (pinfunction "1_1") (pintype "passive"))
      (node (ref "R202") (pin "2") (pinfunction "2_2") (pintype "passive"))
    )
    (net (code "141") (name "Net-(JP12-Pad3)") (class "Default")
      (node (ref "JP12") (pin "3") (pinfunction "3_3") (pintype "passive"))
      (node (ref "R194") (pin "1") (pinfunction "1_1") (pintype "passive"))
    )
    (net (code "142") (name "Net-(JP15-Pad2)") (class "Default")
      (node (ref "JP15") (pin "2") (pinfunction "2_2") (pintype "passive"))
      (node (ref "R199") (pin "2") (pinfunction "2_2") (pintype "passive"))
      (node (ref "R200") (pin "2") (pinfunction "2_2") (pintype "passive"))
      (node (ref "SJ3") (pin "2") (pinfunction "2_2") (pintype "passive"))
    )
    (net (code "143") (name "Net-(JP101-Pad1)") (class "Default")
      (node (ref "JP101") (pin "1") (pinfunction "1_1") (pintype "passive"))
      (node (ref "R119") (pin "2") (pinfunction "2_2") (pintype "passive"))
    )
    (net (code "144") (name "Net-(JP104-Pad2)") (class "Default")
      (node (ref "JP104") (pin "2") (pinfunction "2_2") (pintype "passive"))
      (node (ref "R136") (pin "2") (pinfunction "2_2") (pintype "passive"))
      (node (ref "R137") (pin "2") (pinfunction "2_2") (pintype "passive"))
      (node (ref "SJ101") (pin "2") (pinfunction "2_2") (pintype "passive"))
    )
    (net (code "145") (name "Net-(JP105-Pad3)") (class "Default")
      (node (ref "JP105") (pin "3") (pinfunction "3_3") (pintype "passive"))
      (node (ref "R138") (pin "1") (pinfunction "1_1") (pintype "passive"))
    )
    (net (code "146") (name "Net-(LED13-PadA)") (class "Default")
      (node (ref "LED13") (pin "A") (pinfunction "A_A") (pintype "passive"))
      (node (ref "LED14") (pin "A") (pinfunction "A_A") (pintype "passive"))
      (node (ref "LED15") (pin "A") (pinfunction "A_A") (pintype "passive"))
      (node (ref "LED16") (pin "A") (pinfunction "A_A") (pintype "passive"))
      (node (ref "LED18") (pin "A") (pinfunction "A_A") (pintype "passive"))
      (node (ref "R188") (pin "1") (pinfunction "1_1") (pintype "passive"))
    )
    (net (code "147") (name "Net-(LED17-C)") (class "Default")
      (node (ref "LED17") (pin "K") (pinfunction "C_K") (pintype "passive"))
      (node (ref "R187") (pin "1") (pinfunction "1_1") (pintype "passive"))
    )
    (net (code "148") (name "Net-(LED101-C)") (class "Default")
      (node (ref "LED101") (pin "K") (pinfunction "C_K") (pintype "passive"))
      (node (ref "R143") (pin "1") (pinfunction "1_1") (pintype "passive"))
    )
    (net (code "149") (name "Net-(LED102-PadA)") (class "Default")
      (node (ref "LED102") (pin "A") (pinfunction "A_A") (pintype "passive"))
      (node (ref "LED103") (pin "A") (pinfunction "A_A") (pintype "passive"))
      (node (ref "LED104") (pin "A") (pinfunction "A_A") (pintype "passive"))
      (node (ref "LED105") (pin "A") (pinfunction "A_A") (pintype "passive"))
      (node (ref "LED106") (pin "A") (pinfunction "A_A") (pintype "passive"))
      (node (ref "R142") (pin "1") (pinfunction "1_1") (pintype "passive"))
    )
    (net (code "150") (name "Net-(Q2-B)") (class "Default")
      (node (ref "Q2") (pin "1") (pinfunction "B_1") (pintype "passive"))
      (node (ref "R8") (pin "1") (pinfunction "1_1") (pintype "passive"))
    )
    (net (code "151") (name "Net-(Q2-C)") (class "Default")
      (node (ref "Q2") (pin "2") (pinfunction "C_2") (pintype "passive"))
      (node (ref "R129") (pin "2") (pinfunction "2_2") (pintype "passive"))
      (node (ref "SJMP") (pin "2") (pinfunction "2_2") (pintype "passive"))
    )
    (net (code "152") (name "Net-(Q3-D)") (class "Default")
      (node (ref "Q3") (pin "3") (pinfunction "D_3") (pintype "passive"))
      (node (ref "R8") (pin "2") (pinfunction "2_2") (pintype "passive"))
    )
    (net (code "153") (name "Net-(Q24-B)") (class "Default")
      (node (ref "Q24") (pin "1") (pinfunction "B_1") (pintype "passive"))
      (node (ref "R189") (pin "2") (pinfunction "2_2") (pintype "passive"))
    )
    (net (code "154") (name "Net-(Q25-B)") (class "Default")
      (node (ref "Q25") (pin "1") (pinfunction "B_1") (pintype "passive"))
      (node (ref "Q25") (pin "2") (pinfunction "C_2") (pintype "passive"))
      (node (ref "Q26") (pin "1") (pinfunction "B_1") (pintype "passive"))
      (node (ref "R184") (pin "1") (pinfunction "1_1") (pintype "passive"))
      (node (ref "R185") (pin "1") (pinfunction "1_1") (pintype "passive"))
      (node (ref "R209") (pin "1") (pinfunction "1_1") (pintype "passive"))
      (node (ref "X9") (pin "2") (pinfunction "S_2") (pintype "passive"))
    )
    (net (code "155") (name "Net-(Q25-E)") (class "Default")
      (node (ref "Q25") (pin "3") (pinfunction "E_3") (pintype "passive"))
      (node (ref "R190") (pin "2") (pinfunction "2_2") (pintype "passive"))
    )
    (net (code "156") (name "Net-(Q26-E)") (class "Default")
      (node (ref "Q26") (pin "3") (pinfunction "E_3") (pintype "passive"))
      (node (ref "R191") (pin "2") (pinfunction "2_2") (pintype "passive"))
    )
    (net (code "157") (name "Net-(Q27-B)") (class "Default")
      (node (ref "Q27") (pin "1") (pinfunction "B_1") (pintype "passive"))
      (node (ref "R182") (pin "1") (pinfunction "1_1") (pintype "passive"))
    )
    (net (code "158") (name "Net-(Q28-B)") (class "Default")
      (node (ref "Q28") (pin "1") (pinfunction "B_1") (pintype "passive"))
      (node (ref "R193") (pin "2") (pinfunction "2_2") (pintype "passive"))
      (node (ref "R214") (pin "1") (pinfunction "1_1") (pintype "passive"))
    )
    (net (code "159") (name "Net-(Q28-E)") (class "Default")
      (node (ref "Q28") (pin "3") (pinfunction "E_3") (pintype "passive"))
      (node (ref "R213") (pin "1") (pinfunction "1_1") (pintype "passive"))
    )
    (net (code "160") (name "Net-(Q29-D)") (class "Default")
      (node (ref "Q29") (pin "3") (pinfunction "D_3") (pintype "passive"))
      (node (ref "R194") (pin "2") (pinfunction "2_2") (pintype "passive"))
    )
    (net (code "161") (name "Net-(Q30-S)") (class "Default")
      (node (ref "Q30") (pin "2") (pinfunction "S_2") (pintype "passive"))
      (node (ref "R215") (pin "2") (pinfunction "2_2") (pintype "passive"))
    )
    (net (code "162") (name "Net-(Q32-B)") (class "Default")
      (node (ref "Q32") (pin "1") (pinfunction "B_1") (pintype "passive"))
      (node (ref "R217") (pin "1") (pinfunction "1_1") (pintype "passive"))
    )
    (net (code "163") (name "Net-(Q32-C)") (class "Default")
      (node (ref "Q32") (pin "2") (pinfunction "C_2") (pintype "passive"))
      (node (ref "R168") (pin "2") (pinfunction "2_2") (pintype "passive"))
      (node (ref "SJMP3") (pin "2") (pinfunction "2_2") (pintype "passive"))
    )
    (net (code "164") (name "Net-(Q33-D)") (class "Default")
      (node (ref "Q33") (pin "3") (pinfunction "D_3") (pintype "passive"))
      (node (ref "R217") (pin "2") (pinfunction "2_2") (pintype "passive"))
    )
    (net (code "165") (name "Net-(Q101-B)") (class "Default")
      (node (ref "Q101") (pin "1") (pinfunction "B_1") (pintype "passive"))
      (node (ref "Q102") (pin "1") (pinfunction "B_1") (pintype "passive"))
      (node (ref "Q102") (pin "2") (pinfunction "C_2") (pintype "passive"))
      (node (ref "R101") (pin "1") (pinfunction "1_1") (pintype "passive"))
      (node (ref "R103") (pin "1") (pinfunction "1_1") (pintype "passive"))
      (node (ref "R104") (pin "1") (pinfunction "1_1") (pintype "passive"))
      (node (ref "X102") (pin "2") (pinfunction "S_2") (pintype "passive"))
    )
    (net (code "166") (name "Net-(Q101-E)") (class "Default")
      (node (ref "Q101") (pin "3") (pinfunction "E_3") (pintype "passive"))
      (node (ref "R102") (pin "2") (pinfunction "2_2") (pintype "passive"))
    )
    (net (code "167") (name "Net-(Q102-E)") (class "Default")
      (node (ref "Q102") (pin "3") (pinfunction "E_3") (pintype "passive"))
      (node (ref "R106") (pin "2") (pinfunction "2_2") (pintype "passive"))
    )
    (net (code "168") (name "Net-(Q103-B)") (class "Default")
      (node (ref "Q103") (pin "1") (pinfunction "B_1") (pintype "passive"))
      (node (ref "R116") (pin "2") (pinfunction "2_2") (pintype "passive"))
      (node (ref "R6") (pin "1") (pinfunction "1_1") (pintype "passive"))
    )
    (net (code "169") (name "Net-(Q103-E)") (class "Default")
      (node (ref "Q103") (pin "3") (pinfunction "E_3") (pintype "passive"))
      (node (ref "R5") (pin "1") (pinfunction "1_1") (pintype "passive"))
    )
    (net (code "170") (name "Net-(Q104-B)") (class "Default")
      (node (ref "Q104") (pin "1") (pinfunction "B_1") (pintype "passive"))
      (node (ref "R128") (pin "2") (pinfunction "2_2") (pintype "passive"))
    )
    (net (code "171") (name "Net-(Q105-B)") (class "Default")
      (node (ref "Q105") (pin "1") (pinfunction "B_1") (pintype "passive"))
      (node (ref "R126") (pin "1") (pinfunction "1_1") (pintype "passive"))
    )
    (net (code "172") (name "Net-(Q106-S)") (class "Default")
      (node (ref "Q106") (pin "2") (pinfunction "S_2") (pintype "passive"))
      (node (ref "R4") (pin "2") (pinfunction "2_2") (pintype "passive"))
    )
    (net (code "173") (name "Net-(Q107-D)") (class "Default")
      (node (ref "Q107") (pin "3") (pinfunction "D_3") (pintype "passive"))
      (node (ref "R138") (pin "2") (pinfunction "2_2") (pintype "passive"))
    )
    (net (code "174") (name "Net-(R115-Pad1)") (class "Default")
      (node (ref "R115") (pin "1") (pinfunction "1_1") (pintype "passive"))
      (node (ref "X101") (pin "21") (pinfunction "21_21") (pintype "passive"))
    )
    (net (code "175") (name "Net-(R127-Pad2)") (class "Default")
      (node (ref "R127") (pin "2") (pinfunction "2_2") (pintype "passive"))
      (node (ref "R129") (pin "1") (pinfunction "1_1") (pintype "passive"))
    )
    (net (code "176") (name "Net-(R140-Pad2)") (class "Default")
      (node (ref "R140") (pin "2") (pinfunction "2_2") (pintype "passive"))
      (node (ref "X101") (pin "16") (pinfunction "16_16") (pintype "passive"))
    )
    (net (code "177") (name "Net-(R166-Pad2)") (class "Default")
      (node (ref "R166") (pin "2") (pinfunction "2_2") (pintype "passive"))
      (node (ref "R168") (pin "1") (pinfunction "1_1") (pintype "passive"))
    )
    (net (code "178") (name "Net-(R186-Pad1)") (class "Default")
      (node (ref "R186") (pin "1") (pinfunction "1_1") (pintype "passive"))
      (node (ref "X7") (pin "21") (pinfunction "21_21") (pintype "passive"))
    )
    (net (code "179") (name "Net-(R198-Pad2)") (class "Default")
      (node (ref "R198") (pin "2") (pinfunction "2_2") (pintype "passive"))
      (node (ref "X7") (pin "16") (pinfunction "16_16") (pintype "passive"))
    )
    (net (code "180") (name "V+") (class "Default")
      (node (ref "D1") (pin "1") (pinfunction "+_1") (pintype "passive"))
      (node (ref "D43") (pin "1") (pinfunction "+_1") (pintype "passive"))
      (node (ref "Q105") (pin "3") (pinfunction "E_3") (pintype "passive"))
      (node (ref "Q2") (pin "3") (pinfunction "E_3") (pintype "passive"))
      (node (ref "Q24") (pin "3") (pinfunction "E_3") (pintype "passive"))
      (node (ref "Q27") (pin "3") (pinfunction "E_3") (pintype "passive"))
      (node (ref "Q32") (pin "3") (pinfunction "E_3") (pintype "passive"))
      (node (ref "SJMP") (pin "1") (pinfunction "1_1") (pintype "passive"))
      (node (ref "SJMP3") (pin "1") (pinfunction "1_1") (pintype "passive"))
      (node (ref "X101") (pin "6") (pinfunction "6_6") (pintype "passive"))
      (node (ref "X7") (pin "6") (pinfunction "6_6") (pintype "passive"))
    )
    (net (code "181") (name "VCC") (class "Default")
      (node (ref "6V") (pin "TP") (pinfunction "PP_TP") (pintype "input"))
      (node (ref "6V3") (pin "TP") (pinfunction "PP_TP") (pintype "input"))
      (node (ref "C104") (pin "1") (pinfunction "1_1") (pintype "passive"))
      (node (ref "C29") (pin "1") (pinfunction "1_1") (pintype "passive"))
      (node (ref "IC101") (pin "8") (pinfunction "V+_8") (pintype "power_in"))
      (node (ref "IC102") (pin "1") (pinfunction "OUT_1") (pintype "passive"))
      (node (ref "IC108") (pin "3") (pinfunction "V+_3") (pintype "power_in"))
      (node (ref "IC22") (pin "3") (pinfunction "V+_3") (pintype "power_in"))
      (node (ref "IC23") (pin "1") (pinfunction "OUT_1") (pintype "passive"))
      (node (ref "IC27") (pin "8") (pinfunction "V+_8") (pintype "power_in"))
      (node (ref "R113") (pin "2") (pinfunction "2_2") (pintype "passive"))
      (node (ref "R121") (pin "2") (pinfunction "2_2") (pintype "passive"))
      (node (ref "R124") (pin "1") (pinfunction "1_1") (pintype "passive"))
      (node (ref "R131") (pin "2") (pinfunction "2_2") (pintype "passive"))
      (node (ref "R142") (pin "2") (pinfunction "2_2") (pintype "passive"))
      (node (ref "R175") (pin "2") (pinfunction "2_2") (pintype "passive"))
      (node (ref "R178") (pin "2") (pinfunction "2_2") (pintype "passive"))
      (node (ref "R181") (pin "1") (pinfunction "1_1") (pintype "passive"))
      (node (ref "R188") (pin "2") (pinfunction "2_2") (pintype "passive"))
      (node (ref "R207") (pin "2") (pinfunction "2_2") (pintype "passive"))
    )
    (net (code "182") (name "unconnected-(C63-Pad1)") (class "Default")
      (node (ref "C63") (pin "1") (pinfunction "1_1") (pintype "passive"))
    )
    (net (code "183") (name "unconnected-(C63-Pad2)") (class "Default")
      (node (ref "C63") (pin "2") (pinfunction "2_2") (pintype "passive"))
    )
    (net (code "184") (name "unconnected-(D74-+-Pad1)") (class "Default")
      (node (ref "D74") (pin "1") (pinfunction "+_1") (pintype "passive"))
    )
    (net (code "185") (name "unconnected-(D74---Pad2)") (class "Default")
      (node (ref "D74") (pin "2") (pinfunction "-_2") (pintype "passive"))
    )
    (net (code "186") (name "unconnected-(IC19A-Q6-Pad7)") (class "Default")
      (node (ref "IC19") (pin "7") (pinfunction "Q6_7") (pintype "output"))
    )
    (net (code "187") (name "unconnected-(IC19A-Q7-Pad4)") (class "Default")
      (node (ref "IC19") (pin "4") (pinfunction "Q7_4") (pintype "output"))
    )
    (net (code "188") (name "unconnected-(IC19A-Q8-Pad9)") (class "Default")
      (node (ref "IC19") (pin "9") (pinfunction "Q8_9") (pintype "output"))
    )
    (net (code "189") (name "unconnected-(IC19A-Q9-Pad5)") (class "Default")
      (node (ref "IC19") (pin "5") (pinfunction "Q9_5") (pintype "output"))
    )
    (net (code "190") (name "unconnected-(IC24-DIS-Pad7)") (class "Default")
      (node (ref "IC24") (pin "7") (pinfunction "DIS_7") (pintype "input"))
    )
    (net (code "191") (name "unconnected-(IC25A-~{Q}-Pad7)") (class "Default")
      (node (ref "IC25") (pin "7") (pinfunction "~{Q}_7") (pintype "output"))
    )
    (net (code "192") (name "unconnected-(IC25B-Q-Pad10)") (class "Default")
      (node (ref "IC25") (pin "10") (pinfunction "Q_10") (pintype "output"))
    )
    (net (code "193") (name "unconnected-(IC105A-Q6-Pad7)") (class "Default")
      (node (ref "IC105") (pin "7") (pinfunction "Q6_7") (pintype "output"))
    )
    (net (code "194") (name "unconnected-(IC105A-Q7-Pad4)") (class "Default")
      (node (ref "IC105") (pin "4") (pinfunction "Q7_4") (pintype "output"))
    )
    (net (code "195") (name "unconnected-(IC105A-Q8-Pad9)") (class "Default")
      (node (ref "IC105") (pin "9") (pinfunction "Q8_9") (pintype "output"))
    )
    (net (code "196") (name "unconnected-(IC105A-Q9-Pad5)") (class "Default")
      (node (ref "IC105") (pin "5") (pinfunction "Q9_5") (pintype "output"))
    )
    (net (code "197") (name "unconnected-(IC110-DIS-Pad7)") (class "Default")
      (node (ref "IC110") (pin "7") (pinfunction "DIS_7") (pintype "input"))
    )
    (net (code "198") (name "unconnected-(IC111A-~{Q}-Pad7)") (class "Default")
      (node (ref "IC111") (pin "7") (pinfunction "~{Q}_7") (pintype "output"))
    )
    (net (code "199") (name "unconnected-(IC111B-Q-Pad10)") (class "Default")
      (node (ref "IC111") (pin "10") (pinfunction "Q_10") (pintype "output"))
    )
    (net (code "200") (name "unconnected-(X7-Pad20)") (class "Default")
      (node (ref "X7") (pin "20") (pinfunction "20_20") (pintype "passive"))
    )
    (net (code "201") (name "unconnected-(X7-Pad24)") (class "Default")
      (node (ref "X7") (pin "24") (pinfunction "24_24") (pintype "passive"))
    )
    (net (code "202") (name "unconnected-(X101-Pad20)") (class "Default")
      (node (ref "X101") (pin "20") (pinfunction "20_20") (pintype "passive"))
    )
    (net (code "203") (name "unconnected-(X101-Pad24)") (class "Default")
      (node (ref "X101") (pin "24") (pinfunction "24_24") (pintype "passive"))
    )
  )
)
